# 1-13-2013.net
KiCad netlist of a schematic drawn in EAGLE
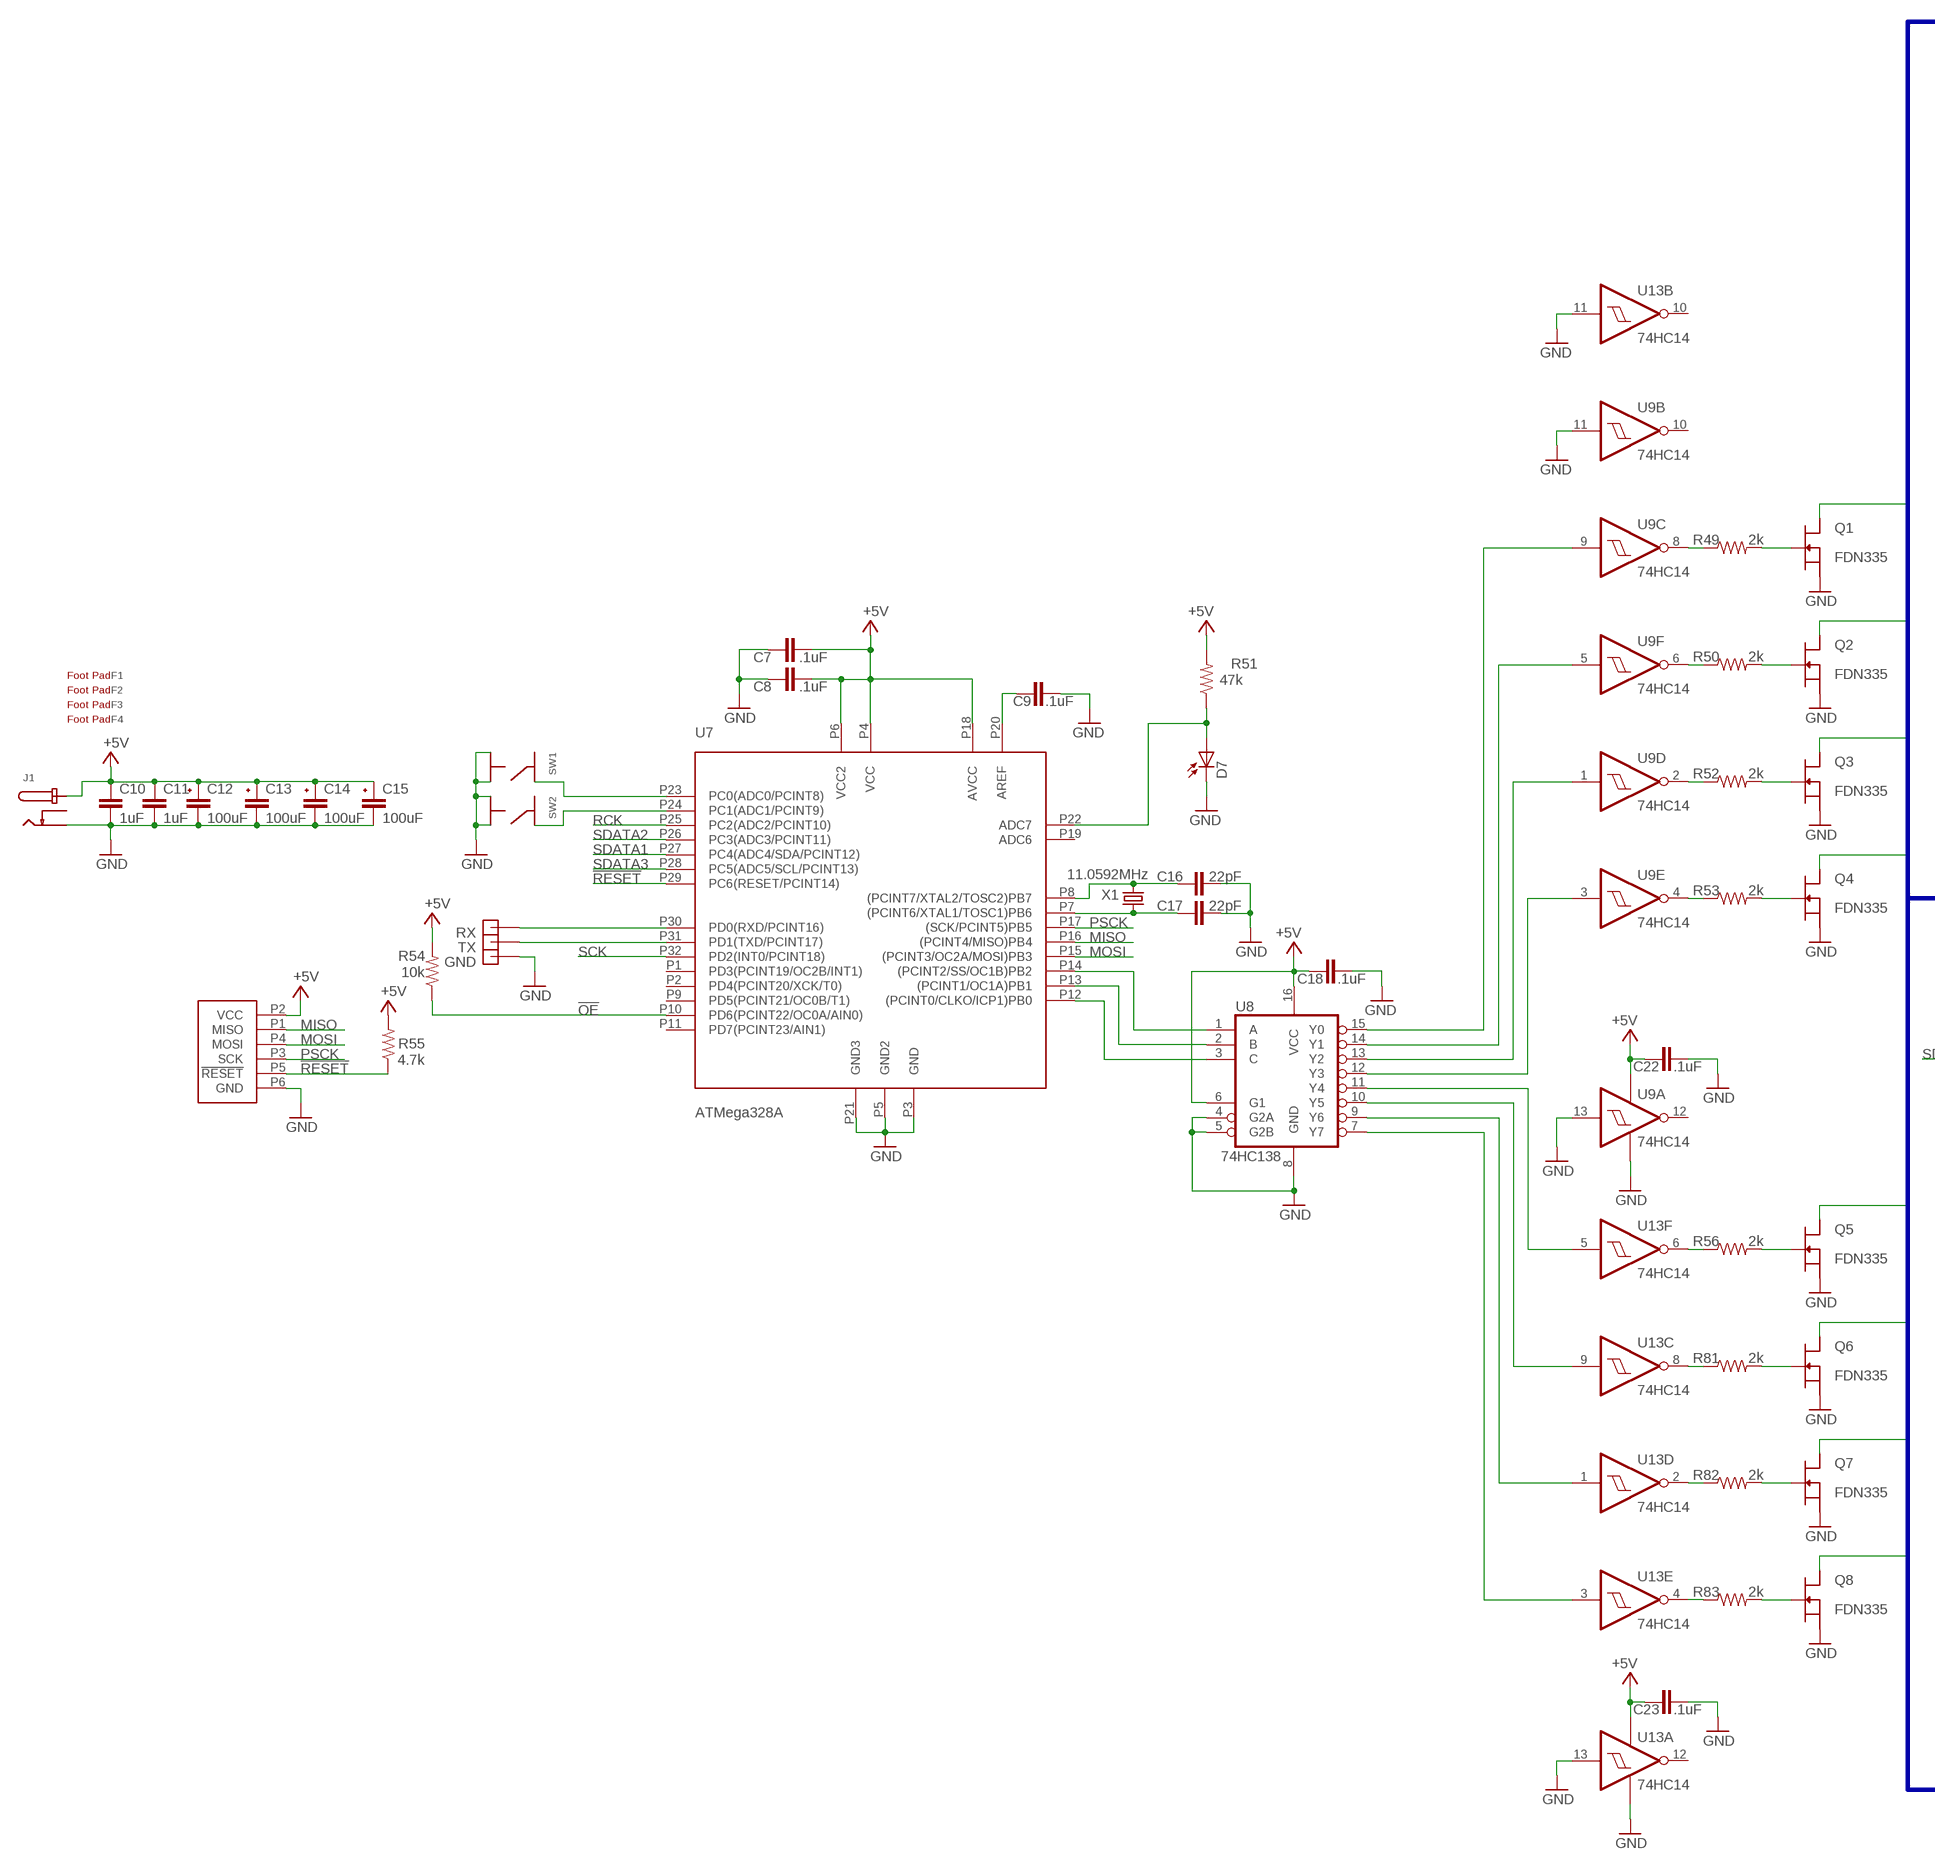
[diagram p0: schematic, sheet 1, part 1 of 2]
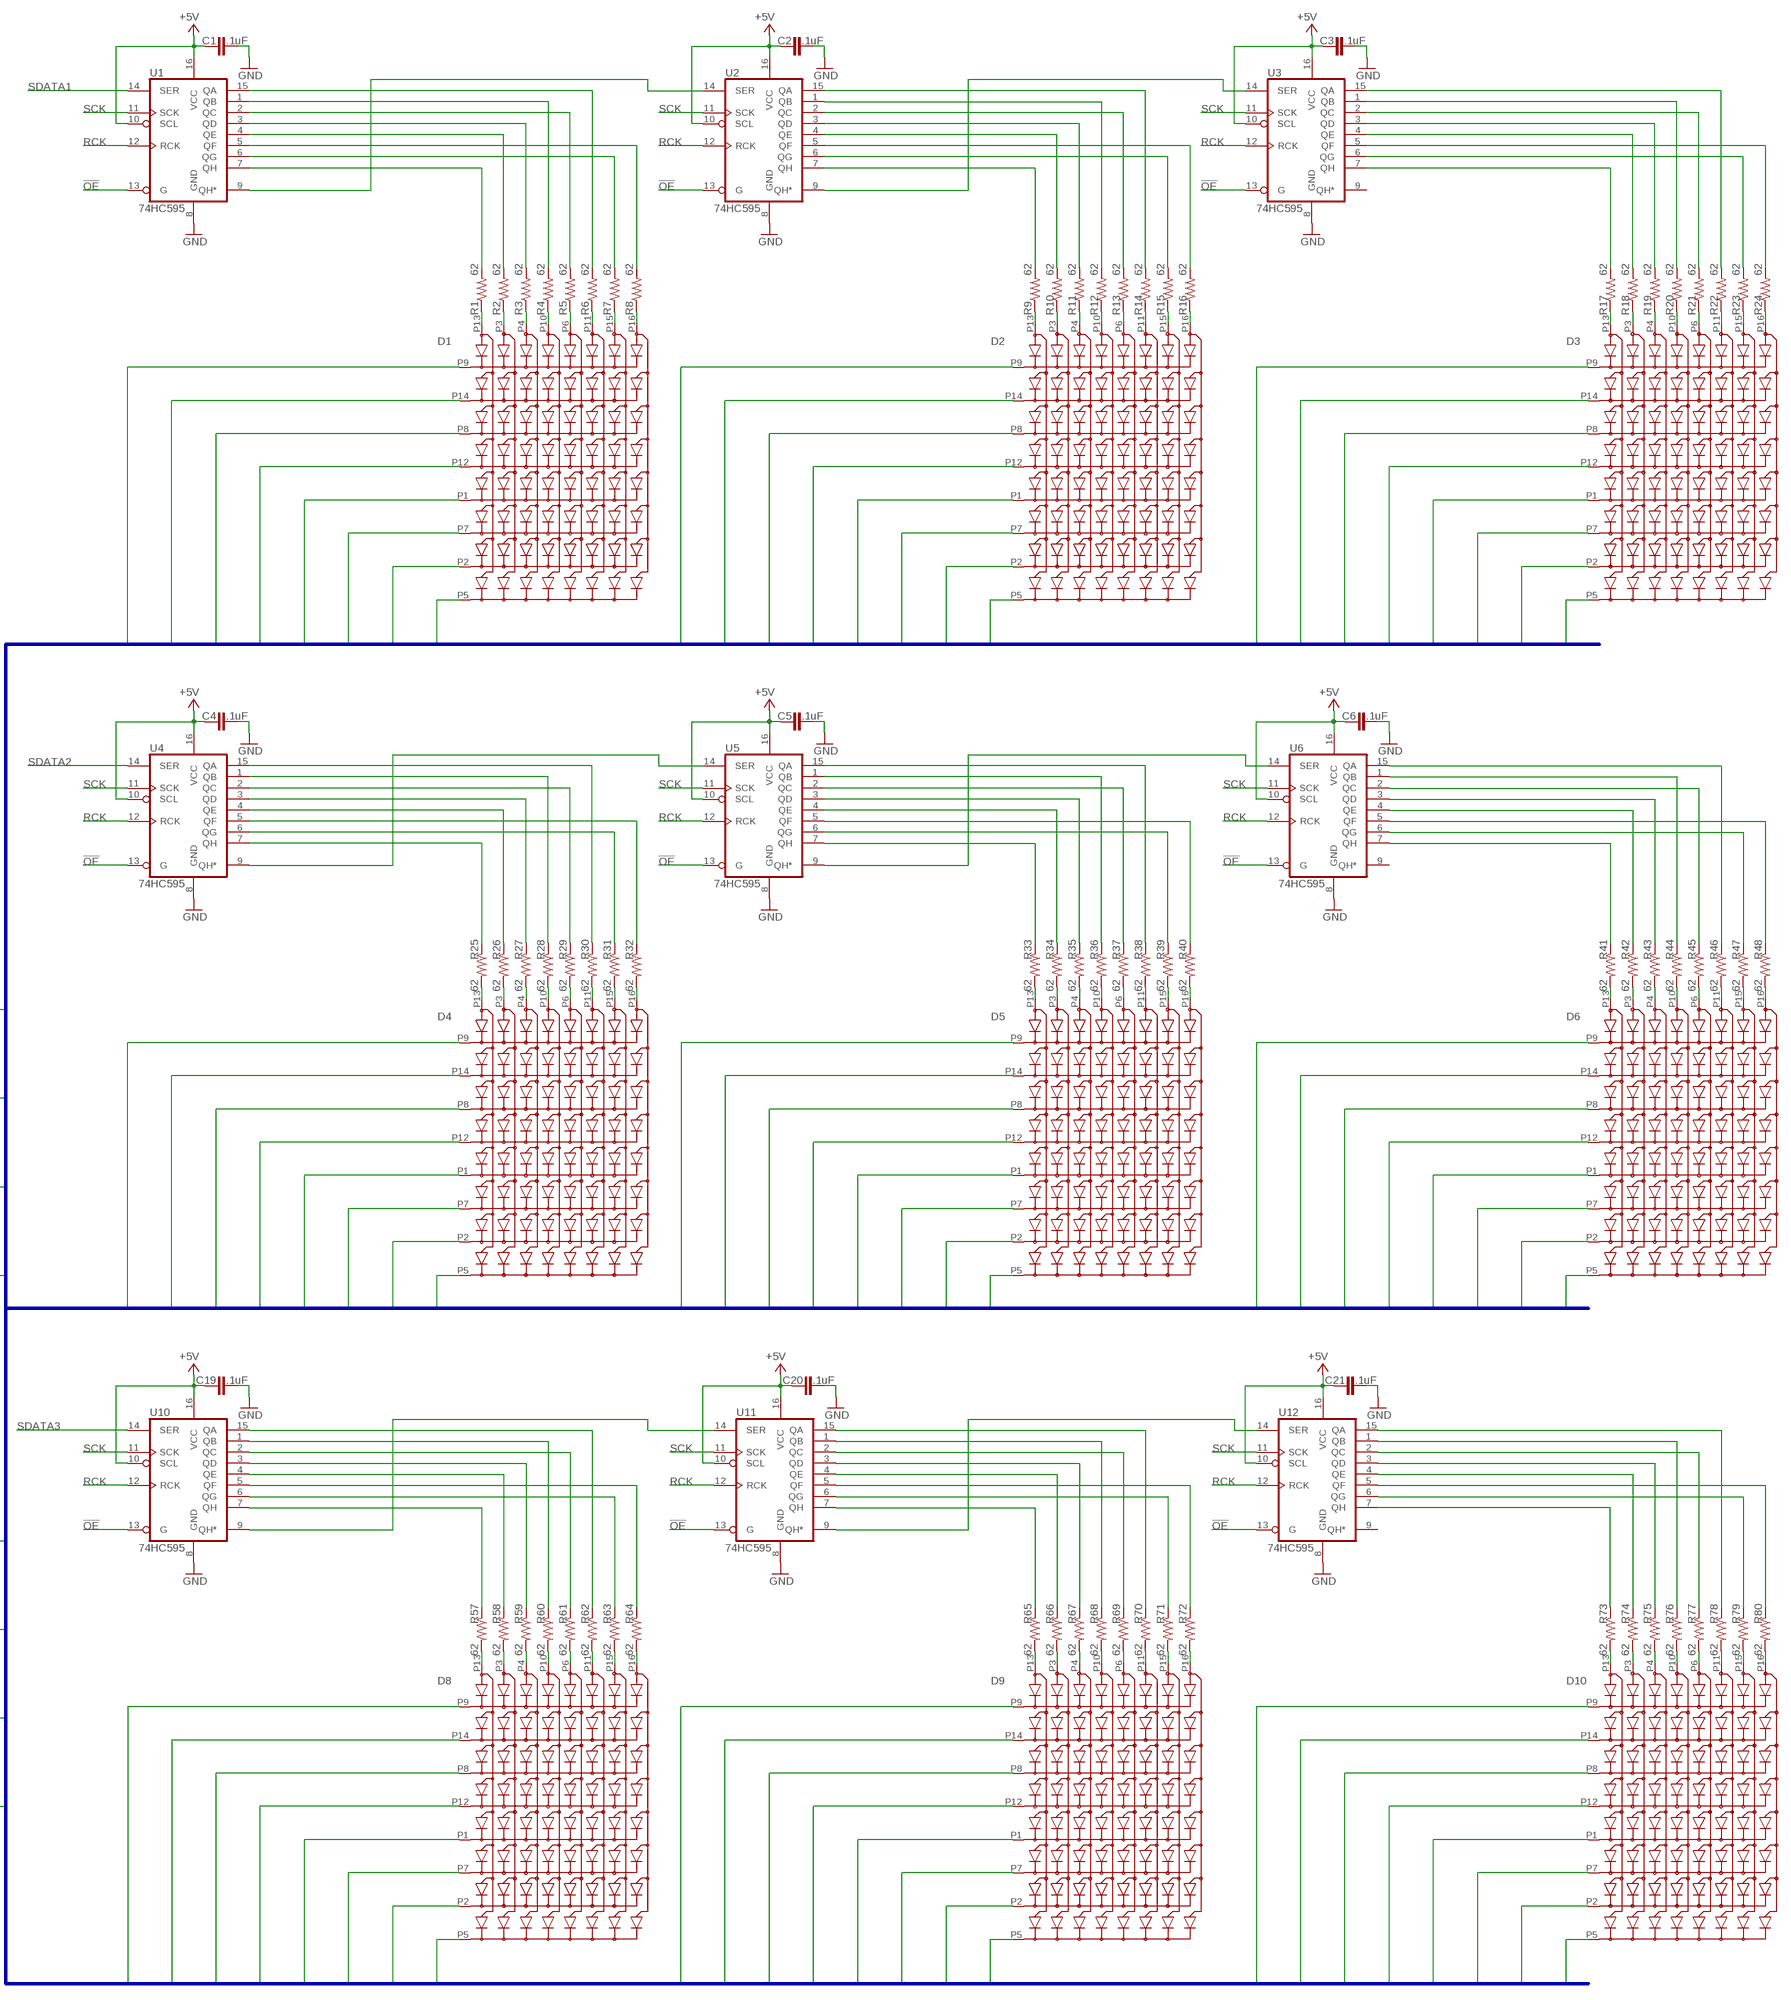
[diagram p1: schematic, sheet 1, part 2 of 2]

(export (version "E")
  (design (tool "Eeschema 10.0.6"))
  (components
    (comp (ref "C1")
      (value ".1uF")
      (footprint "eagle-import:0603_1608METRIC")
      (fields
        (field (name "DISTRIBUTORPARTNO") "478-1239-1-ND")
        (field (name "MANUFACTURER") "AVX Corporation")
        (field (name "TOLERANCE") "10%")
        (field (name "MNT-TYPE") "SM")
      )
      (libsource (lib "eagle-import") (part "CAPACITOR-.1UF"))
    )
    (comp (ref "C2")
      (value ".1uF")
      (footprint "eagle-import:0603_1608METRIC")
      (fields
        (field (name "DISTRIBUTORPARTNO") "478-1239-1-ND")
        (field (name "MANUFACTURER") "AVX Corporation")
        (field (name "TOLERANCE") "10%")
        (field (name "MNT-TYPE") "SM")
      )
      (libsource (lib "eagle-import") (part "CAPACITOR-.1UF"))
    )
    (comp (ref "C3")
      (value ".1uF")
      (footprint "eagle-import:0603_1608METRIC")
      (fields
        (field (name "DISTRIBUTORPARTNO") "478-1239-1-ND")
        (field (name "MANUFACTURER") "AVX Corporation")
        (field (name "TOLERANCE") "10%")
        (field (name "MNT-TYPE") "SM")
      )
      (libsource (lib "eagle-import") (part "CAPACITOR-.1UF"))
    )
    (comp (ref "C4")
      (value ".1uF")
      (footprint "eagle-import:0603_1608METRIC")
      (fields
        (field (name "DISTRIBUTORPARTNO") "478-1239-1-ND")
        (field (name "MANUFACTURER") "AVX Corporation")
        (field (name "TOLERANCE") "10%")
        (field (name "MNT-TYPE") "SM")
      )
      (libsource (lib "eagle-import") (part "CAPACITOR-.1UF"))
    )
    (comp (ref "C5")
      (value ".1uF")
      (footprint "eagle-import:0603_1608METRIC")
      (fields
        (field (name "DISTRIBUTORPARTNO") "478-1239-1-ND")
        (field (name "MANUFACTURER") "AVX Corporation")
        (field (name "TOLERANCE") "10%")
        (field (name "MNT-TYPE") "SM")
      )
      (libsource (lib "eagle-import") (part "CAPACITOR-.1UF"))
    )
    (comp (ref "C6")
      (value ".1uF")
      (footprint "eagle-import:0603_1608METRIC")
      (fields
        (field (name "DISTRIBUTORPARTNO") "478-1239-1-ND")
        (field (name "MANUFACTURER") "AVX Corporation")
        (field (name "TOLERANCE") "10%")
        (field (name "MNT-TYPE") "SM")
      )
      (libsource (lib "eagle-import") (part "CAPACITOR-.1UF"))
    )
    (comp (ref "C7")
      (value ".1uF")
      (footprint "eagle-import:0603_1608METRIC")
      (fields
        (field (name "DISTRIBUTORPARTNO") "478-1239-1-ND")
        (field (name "MANUFACTURER") "AVX Corporation")
        (field (name "TOLERANCE") "10%")
        (field (name "MNT-TYPE") "SM")
      )
      (libsource (lib "eagle-import") (part "CAPACITOR-.1UF"))
    )
    (comp (ref "C8")
      (value ".1uF")
      (footprint "eagle-import:0603_1608METRIC")
      (fields
        (field (name "DISTRIBUTORPARTNO") "478-1239-1-ND")
        (field (name "MANUFACTURER") "AVX Corporation")
        (field (name "TOLERANCE") "10%")
        (field (name "MNT-TYPE") "SM")
      )
      (libsource (lib "eagle-import") (part "CAPACITOR-.1UF"))
    )
    (comp (ref "C9")
      (value ".1uF")
      (footprint "eagle-import:0603_1608METRIC")
      (fields
        (field (name "DISTRIBUTORPARTNO") "478-1239-1-ND")
        (field (name "MANUFACTURER") "AVX Corporation")
        (field (name "TOLERANCE") "10%")
        (field (name "MNT-TYPE") "SM")
      )
      (libsource (lib "eagle-import") (part "CAPACITOR-.1UF"))
    )
    (comp (ref "C10")
      (value "1uF")
      (footprint "eagle-import:0603_1608METRIC")
      (fields
        (field (name "DISTRIBUTORPARTNO") "445-1328-1-ND")
        (field (name "MANUFACTURER") "TDK CORPORATION")
        (field (name "TOLERANCE") "20%")
      )
      (libsource (lib "eagle-import") (part "CAPACITOR-1UF"))
    )
    (comp (ref "C11")
      (value "1uF")
      (footprint "eagle-import:0603_1608METRIC")
      (fields
        (field (name "DISTRIBUTORPARTNO") "445-1328-1-ND")
        (field (name "MANUFACTURER") "TDK CORPORATION")
        (field (name "TOLERANCE") "20%")
      )
      (libsource (lib "eagle-import") (part "CAPACITOR-1UF"))
    )
    (comp (ref "C12")
      (value "100uF")
      (footprint "eagle-import:CAP-UWX-6.3")
      (fields
        (field (name "DISTRIBUTORPARTNO") "493-2105-1-ND")
        (field (name "MANPARTNO") "UWX1C101MCL1GB")
        (field (name "MANUFACTURER") "Nichicon")
      )
      (libsource (lib "eagle-import") (part "ELEC-100UF-SMT"))
    )
    (comp (ref "C13")
      (value "100uF")
      (footprint "eagle-import:CAP-UWX-6.3")
      (fields
        (field (name "DISTRIBUTORPARTNO") "493-2105-1-ND")
        (field (name "MANPARTNO") "UWX1C101MCL1GB")
        (field (name "MANUFACTURER") "Nichicon")
      )
      (libsource (lib "eagle-import") (part "ELEC-100UF-SMT"))
    )
    (comp (ref "C14")
      (value "100uF")
      (footprint "eagle-import:CAP-UWX-6.3")
      (description "CAP ALUM 100UF 16V 20% SMD")
      (fields
        (field (name "DISTRIBUTORPARTNO") "493-2105-1-ND")
        (field (name "MANPARTNO") "UWX1C101MCL1GB")
        (field (name "MANUFACTURER") "Nichicon")
        (field (name "DISTRIBUTOR") "Digikey")
        (field (name "DISTRIBUTORPARTNO_1") "493-2105-1-ND")
        (field (name "MANPARTNO_1") "UWX1C101MCL1GB")
        (field (name "MANUFACTURER_1") "Nichicon")
        (field (name "MNT-TYPE") "SM")
        (field (name "NO-PINS") "2")
        (field (name "PACKAGE") "RADIAL-SMT")
      )
      (libsource (lib "eagle-import") (part "ELEC-100UF-SMT"))
    )
    (comp (ref "C15")
      (value "100uF")
      (footprint "eagle-import:CAP-UWX-6.3")
      (description "CAP ALUM 100UF 16V 20% SMD")
      (fields
        (field (name "DISTRIBUTORPARTNO") "493-2105-1-ND")
        (field (name "MANPARTNO") "UWX1C101MCL1GB")
        (field (name "MANUFACTURER") "Nichicon")
        (field (name "DISTRIBUTOR") "Digikey")
        (field (name "DISTRIBUTORPARTNO_1") "493-2105-1-ND")
        (field (name "MANPARTNO_1") "UWX1C101MCL1GB")
        (field (name "MANUFACTURER_1") "Nichicon")
        (field (name "MNT-TYPE") "SM")
        (field (name "NO-PINS") "2")
        (field (name "PACKAGE") "RADIAL-SMT")
      )
      (libsource (lib "eagle-import") (part "ELEC-100UF-SMT"))
    )
    (comp (ref "C16")
      (value "22pF")
      (footprint "eagle-import:0603_1608METRIC")
      (description "CAP CER 22PF 25V 5% NP0 0603")
      (fields
        (field (name "DISTRIBUTORPARTNO") "478-6200-1-ND")
        (field (name "MANPARTNO") "06033A220JAT2A ")
        (field (name "MANUFACTURER") "AVX Corporation")
        (field (name "DISTRIBUTORPARTNO_1") "478-6200-1-ND")
        (field (name "MANUFACTURER_1") "AVX Corporation")
        (field (name "VOLTAGE") "25V")
      )
      (libsource (lib "eagle-import") (part "CAPACITOR-22PF"))
    )
    (comp (ref "C17")
      (value "22pF")
      (footprint "eagle-import:0603_1608METRIC")
      (description "CAP CER 22PF 25V 5% NP0 0603")
      (fields
        (field (name "DISTRIBUTORPARTNO") "478-6200-1-ND")
        (field (name "MANPARTNO") "06033A220JAT2A ")
        (field (name "MANUFACTURER") "AVX Corporation")
        (field (name "DISTRIBUTORPARTNO_1") "478-6200-1-ND")
        (field (name "MANUFACTURER_1") "AVX Corporation")
        (field (name "VOLTAGE") "25V")
      )
      (libsource (lib "eagle-import") (part "CAPACITOR-22PF"))
    )
    (comp (ref "C18")
      (value ".1uF")
      (footprint "eagle-import:0603_1608METRIC")
      (fields
        (field (name "DISTRIBUTORPARTNO") "478-1239-1-ND")
        (field (name "MANUFACTURER") "AVX Corporation")
        (field (name "TOLERANCE") "10%")
        (field (name "MNT-TYPE") "SM")
      )
      (libsource (lib "eagle-import") (part "CAPACITOR-.1UF"))
    )
    (comp (ref "C19")
      (value ".1uF")
      (footprint "eagle-import:0603_1608METRIC")
      (fields
        (field (name "DISTRIBUTORPARTNO") "478-1239-1-ND")
        (field (name "MANUFACTURER") "AVX Corporation")
        (field (name "TOLERANCE") "10%")
        (field (name "MNT-TYPE") "SM")
      )
      (libsource (lib "eagle-import") (part "CAPACITOR-.1UF"))
    )
    (comp (ref "C20")
      (value ".1uF")
      (footprint "eagle-import:0603_1608METRIC")
      (fields
        (field (name "DISTRIBUTORPARTNO") "478-1239-1-ND")
        (field (name "MANUFACTURER") "AVX Corporation")
        (field (name "TOLERANCE") "10%")
        (field (name "MNT-TYPE") "SM")
      )
      (libsource (lib "eagle-import") (part "CAPACITOR-.1UF"))
    )
    (comp (ref "C21")
      (value ".1uF")
      (footprint "eagle-import:0603_1608METRIC")
      (fields
        (field (name "DISTRIBUTORPARTNO") "478-1239-1-ND")
        (field (name "MANUFACTURER") "AVX Corporation")
        (field (name "TOLERANCE") "10%")
        (field (name "MNT-TYPE") "SM")
      )
      (libsource (lib "eagle-import") (part "CAPACITOR-.1UF"))
    )
    (comp (ref "C22")
      (value ".1uF")
      (footprint "eagle-import:0603_1608METRIC")
      (fields
        (field (name "DISTRIBUTORPARTNO") "478-1239-1-ND")
        (field (name "MANUFACTURER") "AVX Corporation")
        (field (name "TOLERANCE") "10%")
        (field (name "MNT-TYPE") "SM")
      )
      (libsource (lib "eagle-import") (part "CAPACITOR-.1UF"))
    )
    (comp (ref "C23")
      (value ".1uF")
      (footprint "eagle-import:0603_1608METRIC")
      (fields
        (field (name "DISTRIBUTORPARTNO") "478-1239-1-ND")
        (field (name "MANUFACTURER") "AVX Corporation")
        (field (name "TOLERANCE") "10%")
        (field (name "MNT-TYPE") "SM")
      )
      (libsource (lib "eagle-import") (part "CAPACITOR-.1UF"))
    )
    (comp (ref "D1")
      (value "WHITE")
      (footprint "eagle-import:HS-2085BX")
      (fields
        (field (name "DISTRIBUTORPARTNO") "HS-2085AWND")
        (field (name "MANUFACTURER") "XINDALI ELECTRONICS")
      )
      (libsource (lib "eagle-import") (part "HS-2085AND-W"))
    )
    (comp (ref "D2")
      (value "WHITE")
      (footprint "eagle-import:HS-2085BX")
      (fields
        (field (name "DISTRIBUTORPARTNO") "HS-2085AWND")
        (field (name "MANUFACTURER") "XINDALI ELECTRONICS")
      )
      (libsource (lib "eagle-import") (part "HS-2085AND-W"))
    )
    (comp (ref "D3")
      (value "WHITE")
      (footprint "eagle-import:HS-2085BX")
      (fields
        (field (name "DISTRIBUTORPARTNO") "HS-2085AWND")
        (field (name "MANUFACTURER") "XINDALI ELECTRONICS")
      )
      (libsource (lib "eagle-import") (part "HS-2085AND-W"))
    )
    (comp (ref "D4")
      (value "WHITE")
      (footprint "eagle-import:HS-2085BX")
      (fields
        (field (name "DISTRIBUTORPARTNO") "HS-2085AWND")
        (field (name "MANUFACTURER") "XINDALI ELECTRONICS")
      )
      (libsource (lib "eagle-import") (part "HS-2085AND-W"))
    )
    (comp (ref "D5")
      (value "WHITE")
      (footprint "eagle-import:HS-2085BX")
      (fields
        (field (name "DISTRIBUTORPARTNO") "HS-2085AWND")
        (field (name "MANUFACTURER") "XINDALI ELECTRONICS")
      )
      (libsource (lib "eagle-import") (part "HS-2085AND-W"))
    )
    (comp (ref "D6")
      (value "WHITE")
      (footprint "eagle-import:HS-2085BX")
      (fields
        (field (name "DISTRIBUTORPARTNO") "HS-2085AWND")
        (field (name "MANUFACTURER") "XINDALI ELECTRONICS")
      )
      (libsource (lib "eagle-import") (part "HS-2085AND-W"))
    )
    (comp (ref "D7")
      (value "TEPT4400")
      (footprint "eagle-import:LED3MM")
      (fields
        (field (name "DISTRIBUTORPARTNO") "751-1057-ND")
        (field (name "MANUFACTURER") "Vishay Semiconductors")
      )
      (libsource (lib "eagle-import") (part "TEPT4400"))
    )
    (comp (ref "D8")
      (value "WHITE")
      (footprint "eagle-import:HS-2085BX")
      (fields
        (field (name "DISTRIBUTORPARTNO") "HS-2085AWND")
        (field (name "MANUFACTURER") "XINDALI ELECTRONICS")
      )
      (libsource (lib "eagle-import") (part "HS-2085AND-W"))
    )
    (comp (ref "D9")
      (value "WHITE")
      (footprint "eagle-import:HS-2085BX")
      (fields
        (field (name "DISTRIBUTORPARTNO") "HS-2085AWND")
        (field (name "MANUFACTURER") "XINDALI ELECTRONICS")
      )
      (libsource (lib "eagle-import") (part "HS-2085AND-W"))
    )
    (comp (ref "D10")
      (value "WHITE")
      (footprint "eagle-import:HS-2085BX")
      (fields
        (field (name "DISTRIBUTORPARTNO") "HS-2085AWND")
        (field (name "MANUFACTURER") "XINDALI ELECTRONICS")
      )
      (libsource (lib "eagle-import") (part "HS-2085AND-W"))
    )
    (comp (ref "F1")
      (value "RUBBER-FOOT")
      (footprint "eagle-import:SJ-5518")
      (fields
        (field (name "DISTRIBUTORPARTNO") "SJ5518-0-ND")
        (field (name "MANPARTNO") "SJ-5518 (BLACK)")
        (field (name "MANUFACTURER") "3M")
      )
      (libsource (lib "eagle-import") (part "RUBBER-FOOT"))
    )
    (comp (ref "F2")
      (value "RUBBER-FOOT")
      (footprint "eagle-import:SJ-5518")
      (fields
        (field (name "DISTRIBUTORPARTNO") "SJ5518-0-ND")
        (field (name "MANPARTNO") "SJ-5518 (BLACK)")
        (field (name "MANUFACTURER") "3M")
      )
      (libsource (lib "eagle-import") (part "RUBBER-FOOT"))
    )
    (comp (ref "F3")
      (value "RUBBER-FOOT")
      (footprint "eagle-import:SJ-5518")
      (fields
        (field (name "DISTRIBUTORPARTNO") "SJ5518-0-ND")
        (field (name "MANPARTNO") "SJ-5518 (BLACK)")
        (field (name "MANUFACTURER") "3M")
      )
      (libsource (lib "eagle-import") (part "RUBBER-FOOT"))
    )
    (comp (ref "F4")
      (value "RUBBER-FOOT")
      (footprint "eagle-import:SJ-5518")
      (fields
        (field (name "DISTRIBUTORPARTNO") "SJ5518-0-ND")
        (field (name "MANPARTNO") "SJ-5518 (BLACK)")
        (field (name "MANUFACTURER") "3M")
      )
      (libsource (lib "eagle-import") (part "RUBBER-FOOT"))
    )
    (comp (ref "GND")
      (value "HEADERPIN")
      (footprint "eagle-import:HEADERPIN")
      (libsource (lib "eagle-import") (part "HEADERPIN"))
    )
    (comp (ref "J1")
      (value "DC-BARREL-JACK-SWITCH")
      (footprint "eagle-import:PJ-075DH-SMT-TR")
      (fields
        (field (name "DISTRIBUTORPARTNO") "CP-075DHPJCT-ND")
        (field (name "MANPARTNO") "PJ-075DH-SMT-TR")
        (field (name "MANUFACTURER") "CUI Inc")
      )
      (libsource (lib "eagle-import") (part "DC-BARREL-JACK-SWITCH"))
    )
    (comp (ref "J2")
      (value "PROGHEADER-PINS")
      (footprint "eagle-import:ATMEL-PROGRAMMING-HEADER")
      (fields
        (field (name "DISTRIBUTORPARTNO") "xxSAM1048-50-NDxx")
        (field (name "MANPARTNO") "TSW-150-08-T-D")
        (field (name "MANUFACTURER") "Samtec Inc.")
      )
      (libsource (lib "eagle-import") (part "PROGHEADER-PINS"))
    )
    (comp (ref "Q1")
      (value "FDN335")
      (footprint "eagle-import:SOT23")
      (fields
        (field (name "DISTRIBUTORPARTNO") "FDN335NCT-ND")
        (field (name "MANPARTNO") "FDN335N")
        (field (name "MANUFACTURER") "Fairchild Semiconductor")
      )
      (libsource (lib "eagle-import") (part "FDN335"))
    )
    (comp (ref "Q2")
      (value "FDN335")
      (footprint "eagle-import:SOT23")
      (fields
        (field (name "DISTRIBUTORPARTNO") "FDN335NCT-ND")
        (field (name "MANPARTNO") "FDN335N")
        (field (name "MANUFACTURER") "Fairchild Semiconductor")
      )
      (libsource (lib "eagle-import") (part "FDN335"))
    )
    (comp (ref "Q3")
      (value "FDN335")
      (footprint "eagle-import:SOT23")
      (fields
        (field (name "DISTRIBUTORPARTNO") "FDN335NCT-ND")
        (field (name "MANPARTNO") "FDN335N")
        (field (name "MANUFACTURER") "Fairchild Semiconductor")
      )
      (libsource (lib "eagle-import") (part "FDN335"))
    )
    (comp (ref "Q4")
      (value "FDN335")
      (footprint "eagle-import:SOT23")
      (fields
        (field (name "DISTRIBUTORPARTNO") "FDN335NCT-ND")
        (field (name "MANPARTNO") "FDN335N")
        (field (name "MANUFACTURER") "Fairchild Semiconductor")
      )
      (libsource (lib "eagle-import") (part "FDN335"))
    )
    (comp (ref "Q5")
      (value "FDN335")
      (footprint "eagle-import:SOT23")
      (fields
        (field (name "DISTRIBUTORPARTNO") "FDN335NCT-ND")
        (field (name "MANPARTNO") "FDN335N")
        (field (name "MANUFACTURER") "Fairchild Semiconductor")
      )
      (libsource (lib "eagle-import") (part "FDN335"))
    )
    (comp (ref "Q6")
      (value "FDN335")
      (footprint "eagle-import:SOT23")
      (fields
        (field (name "DISTRIBUTORPARTNO") "FDN335NCT-ND")
        (field (name "MANPARTNO") "FDN335N")
        (field (name "MANUFACTURER") "Fairchild Semiconductor")
      )
      (libsource (lib "eagle-import") (part "FDN335"))
    )
    (comp (ref "Q7")
      (value "FDN335")
      (footprint "eagle-import:SOT23")
      (fields
        (field (name "DISTRIBUTORPARTNO") "FDN335NCT-ND")
        (field (name "MANPARTNO") "FDN335N")
        (field (name "MANUFACTURER") "Fairchild Semiconductor")
      )
      (libsource (lib "eagle-import") (part "FDN335"))
    )
    (comp (ref "Q8")
      (value "FDN335")
      (footprint "eagle-import:SOT23")
      (fields
        (field (name "DISTRIBUTORPARTNO") "FDN335NCT-ND")
        (field (name "MANPARTNO") "FDN335N")
        (field (name "MANUFACTURER") "Fairchild Semiconductor")
      )
      (libsource (lib "eagle-import") (part "FDN335"))
    )
    (comp (ref "R1")
      (value "62")
      (footprint "eagle-import:0603_1608METRIC")
      (fields
        (field (name "DISTRIBUTORPARTNO") "311-62GRCT-ND ")
        (field (name "MANPARTNO") "RC0603JR-0762RL ")
        (field (name "MANUFACTURER") "Yaego")
      )
      (libsource (lib "eagle-import") (part "RESISTOR--5%-060362"))
    )
    (comp (ref "R2")
      (value "62")
      (footprint "eagle-import:0603_1608METRIC")
      (description "RES 62 OHM 1/10W 5% 0603 SMD")
      (fields
        (field (name "DISTRIBUTORPARTNO") "311-62GRCT-ND ")
        (field (name "MANPARTNO") "RC0603JR-0762RL ")
        (field (name "MANUFACTURER") "Yaego")
        (field (name "DISTRIBUTOR") "Digikey")
        (field (name "DISTRIBUTORPARTNO_1") "311-62GRCT-ND ")
        (field (name "MANPARTNO_1") "RC0603JR-0762RL ")
        (field (name "MANUFACTURER_1") "Yaego")
        (field (name "MNT-TYPE") "SM")
        (field (name "NO-PINS") "2")
        (field (name "PACKAGE") "0603 (16080 Metric)")
        (field (name "TOLERANCE") "5%")
      )
      (libsource (lib "eagle-import") (part "RESISTOR--5%-060362"))
    )
    (comp (ref "R3")
      (value "62")
      (footprint "eagle-import:0603_1608METRIC")
      (description "RES 62 OHM 1/10W 5% 0603 SMD")
      (fields
        (field (name "DISTRIBUTORPARTNO") "311-62GRCT-ND ")
        (field (name "MANPARTNO") "RC0603JR-0762RL ")
        (field (name "MANUFACTURER") "Yaego")
        (field (name "DISTRIBUTOR") "Digikey")
        (field (name "DISTRIBUTORPARTNO_1") "311-62GRCT-ND ")
        (field (name "MANPARTNO_1") "RC0603JR-0762RL ")
        (field (name "MANUFACTURER_1") "Yaego")
        (field (name "MNT-TYPE") "SM")
        (field (name "NO-PINS") "2")
        (field (name "PACKAGE") "0603 (16080 Metric)")
        (field (name "TOLERANCE") "5%")
      )
      (libsource (lib "eagle-import") (part "RESISTOR--5%-060362"))
    )
    (comp (ref "R4")
      (value "62")
      (footprint "eagle-import:0603_1608METRIC")
      (description "RES 62 OHM 1/10W 5% 0603 SMD")
      (fields
        (field (name "DISTRIBUTORPARTNO") "311-62GRCT-ND ")
        (field (name "MANPARTNO") "RC0603JR-0762RL ")
        (field (name "MANUFACTURER") "Yaego")
        (field (name "DISTRIBUTOR") "Digikey")
        (field (name "DISTRIBUTORPARTNO_1") "311-62GRCT-ND ")
        (field (name "MANPARTNO_1") "RC0603JR-0762RL ")
        (field (name "MANUFACTURER_1") "Yaego")
        (field (name "MNT-TYPE") "SM")
        (field (name "NO-PINS") "2")
        (field (name "PACKAGE") "0603 (16080 Metric)")
        (field (name "TOLERANCE") "5%")
      )
      (libsource (lib "eagle-import") (part "RESISTOR--5%-060362"))
    )
    (comp (ref "R5")
      (value "62")
      (footprint "eagle-import:0603_1608METRIC")
      (description "RES 62 OHM 1/10W 5% 0603 SMD")
      (fields
        (field (name "DISTRIBUTORPARTNO") "311-62GRCT-ND ")
        (field (name "MANPARTNO") "RC0603JR-0762RL ")
        (field (name "MANUFACTURER") "Yaego")
        (field (name "DISTRIBUTOR") "Digikey")
        (field (name "DISTRIBUTORPARTNO_1") "311-62GRCT-ND ")
        (field (name "MANPARTNO_1") "RC0603JR-0762RL ")
        (field (name "MANUFACTURER_1") "Yaego")
        (field (name "MNT-TYPE") "SM")
        (field (name "NO-PINS") "2")
        (field (name "PACKAGE") "0603 (16080 Metric)")
        (field (name "TOLERANCE") "5%")
      )
      (libsource (lib "eagle-import") (part "RESISTOR--5%-060362"))
    )
    (comp (ref "R6")
      (value "62")
      (footprint "eagle-import:0603_1608METRIC")
      (description "RES 62 OHM 1/10W 5% 0603 SMD")
      (fields
        (field (name "DISTRIBUTORPARTNO") "311-62GRCT-ND ")
        (field (name "MANPARTNO") "RC0603JR-0762RL ")
        (field (name "MANUFACTURER") "Yaego")
        (field (name "DISTRIBUTOR") "Digikey")
        (field (name "DISTRIBUTORPARTNO_1") "311-62GRCT-ND ")
        (field (name "MANPARTNO_1") "RC0603JR-0762RL ")
        (field (name "MANUFACTURER_1") "Yaego")
        (field (name "MNT-TYPE") "SM")
        (field (name "NO-PINS") "2")
        (field (name "PACKAGE") "0603 (16080 Metric)")
        (field (name "TOLERANCE") "5%")
      )
      (libsource (lib "eagle-import") (part "RESISTOR--5%-060362"))
    )
    (comp (ref "R7")
      (value "62")
      (footprint "eagle-import:0603_1608METRIC")
      (description "RES 62 OHM 1/10W 5% 0603 SMD")
      (fields
        (field (name "DISTRIBUTORPARTNO") "311-62GRCT-ND ")
        (field (name "MANPARTNO") "RC0603JR-0762RL ")
        (field (name "MANUFACTURER") "Yaego")
        (field (name "DISTRIBUTOR") "Digikey")
        (field (name "DISTRIBUTORPARTNO_1") "311-62GRCT-ND ")
        (field (name "MANPARTNO_1") "RC0603JR-0762RL ")
        (field (name "MANUFACTURER_1") "Yaego")
        (field (name "MNT-TYPE") "SM")
        (field (name "NO-PINS") "2")
        (field (name "PACKAGE") "0603 (16080 Metric)")
        (field (name "TOLERANCE") "5%")
      )
      (libsource (lib "eagle-import") (part "RESISTOR--5%-060362"))
    )
    (comp (ref "R8")
      (value "62")
      (footprint "eagle-import:0603_1608METRIC")
      (description "RES 62 OHM 1/10W 5% 0603 SMD")
      (fields
        (field (name "DISTRIBUTORPARTNO") "311-62GRCT-ND ")
        (field (name "MANPARTNO") "RC0603JR-0762RL ")
        (field (name "MANUFACTURER") "Yaego")
        (field (name "DISTRIBUTOR") "Digikey")
        (field (name "DISTRIBUTORPARTNO_1") "311-62GRCT-ND ")
        (field (name "MANPARTNO_1") "RC0603JR-0762RL ")
        (field (name "MANUFACTURER_1") "Yaego")
        (field (name "MNT-TYPE") "SM")
        (field (name "NO-PINS") "2")
        (field (name "PACKAGE") "0603 (16080 Metric)")
        (field (name "TOLERANCE") "5%")
      )
      (libsource (lib "eagle-import") (part "RESISTOR--5%-060362"))
    )
    (comp (ref "R9")
      (value "62")
      (footprint "eagle-import:0603_1608METRIC")
      (description "RES 62 OHM 1/10W 5% 0603 SMD")
      (fields
        (field (name "DISTRIBUTORPARTNO") "311-62GRCT-ND ")
        (field (name "MANPARTNO") "RC0603JR-0762RL ")
        (field (name "MANUFACTURER") "Yaego")
        (field (name "DISTRIBUTOR") "Digikey")
        (field (name "DISTRIBUTORPARTNO_1") "311-62GRCT-ND ")
        (field (name "MANPARTNO_1") "RC0603JR-0762RL ")
        (field (name "MANUFACTURER_1") "Yaego")
        (field (name "MNT-TYPE") "SM")
        (field (name "NO-PINS") "2")
        (field (name "PACKAGE") "0603 (16080 Metric)")
        (field (name "TOLERANCE") "5%")
      )
      (libsource (lib "eagle-import") (part "RESISTOR--5%-060362"))
    )
    (comp (ref "R10")
      (value "62")
      (footprint "eagle-import:0603_1608METRIC")
      (description "RES 62 OHM 1/10W 5% 0603 SMD")
      (fields
        (field (name "DISTRIBUTORPARTNO") "311-62GRCT-ND ")
        (field (name "MANPARTNO") "RC0603JR-0762RL ")
        (field (name "MANUFACTURER") "Yaego")
        (field (name "DISTRIBUTOR") "Digikey")
        (field (name "DISTRIBUTORPARTNO_1") "311-62GRCT-ND ")
        (field (name "MANPARTNO_1") "RC0603JR-0762RL ")
        (field (name "MANUFACTURER_1") "Yaego")
        (field (name "MNT-TYPE") "SM")
        (field (name "NO-PINS") "2")
        (field (name "PACKAGE") "0603 (16080 Metric)")
        (field (name "TOLERANCE") "5%")
      )
      (libsource (lib "eagle-import") (part "RESISTOR--5%-060362"))
    )
    (comp (ref "R11")
      (value "62")
      (footprint "eagle-import:0603_1608METRIC")
      (description "RES 62 OHM 1/10W 5% 0603 SMD")
      (fields
        (field (name "DISTRIBUTORPARTNO") "311-62GRCT-ND ")
        (field (name "MANPARTNO") "RC0603JR-0762RL ")
        (field (name "MANUFACTURER") "Yaego")
        (field (name "DISTRIBUTOR") "Digikey")
        (field (name "DISTRIBUTORPARTNO_1") "311-62GRCT-ND ")
        (field (name "MANPARTNO_1") "RC0603JR-0762RL ")
        (field (name "MANUFACTURER_1") "Yaego")
        (field (name "MNT-TYPE") "SM")
        (field (name "NO-PINS") "2")
        (field (name "PACKAGE") "0603 (16080 Metric)")
        (field (name "TOLERANCE") "5%")
      )
      (libsource (lib "eagle-import") (part "RESISTOR--5%-060362"))
    )
    (comp (ref "R12")
      (value "62")
      (footprint "eagle-import:0603_1608METRIC")
      (description "RES 62 OHM 1/10W 5% 0603 SMD")
      (fields
        (field (name "DISTRIBUTORPARTNO") "311-62GRCT-ND ")
        (field (name "MANPARTNO") "RC0603JR-0762RL ")
        (field (name "MANUFACTURER") "Yaego")
        (field (name "DISTRIBUTOR") "Digikey")
        (field (name "DISTRIBUTORPARTNO_1") "311-62GRCT-ND ")
        (field (name "MANPARTNO_1") "RC0603JR-0762RL ")
        (field (name "MANUFACTURER_1") "Yaego")
        (field (name "MNT-TYPE") "SM")
        (field (name "NO-PINS") "2")
        (field (name "PACKAGE") "0603 (16080 Metric)")
        (field (name "TOLERANCE") "5%")
      )
      (libsource (lib "eagle-import") (part "RESISTOR--5%-060362"))
    )
    (comp (ref "R13")
      (value "62")
      (footprint "eagle-import:0603_1608METRIC")
      (description "RES 62 OHM 1/10W 5% 0603 SMD")
      (fields
        (field (name "DISTRIBUTORPARTNO") "311-62GRCT-ND ")
        (field (name "MANPARTNO") "RC0603JR-0762RL ")
        (field (name "MANUFACTURER") "Yaego")
        (field (name "DISTRIBUTOR") "Digikey")
        (field (name "DISTRIBUTORPARTNO_1") "311-62GRCT-ND ")
        (field (name "MANPARTNO_1") "RC0603JR-0762RL ")
        (field (name "MANUFACTURER_1") "Yaego")
        (field (name "MNT-TYPE") "SM")
        (field (name "NO-PINS") "2")
        (field (name "PACKAGE") "0603 (16080 Metric)")
        (field (name "TOLERANCE") "5%")
      )
      (libsource (lib "eagle-import") (part "RESISTOR--5%-060362"))
    )
    (comp (ref "R14")
      (value "62")
      (footprint "eagle-import:0603_1608METRIC")
      (description "RES 62 OHM 1/10W 5% 0603 SMD")
      (fields
        (field (name "DISTRIBUTORPARTNO") "311-62GRCT-ND ")
        (field (name "MANPARTNO") "RC0603JR-0762RL ")
        (field (name "MANUFACTURER") "Yaego")
        (field (name "DISTRIBUTOR") "Digikey")
        (field (name "DISTRIBUTORPARTNO_1") "311-62GRCT-ND ")
        (field (name "MANPARTNO_1") "RC0603JR-0762RL ")
        (field (name "MANUFACTURER_1") "Yaego")
        (field (name "MNT-TYPE") "SM")
        (field (name "NO-PINS") "2")
        (field (name "PACKAGE") "0603 (16080 Metric)")
        (field (name "TOLERANCE") "5%")
      )
      (libsource (lib "eagle-import") (part "RESISTOR--5%-060362"))
    )
    (comp (ref "R15")
      (value "62")
      (footprint "eagle-import:0603_1608METRIC")
      (description "RES 62 OHM 1/10W 5% 0603 SMD")
      (fields
        (field (name "DISTRIBUTORPARTNO") "311-62GRCT-ND ")
        (field (name "MANPARTNO") "RC0603JR-0762RL ")
        (field (name "MANUFACTURER") "Yaego")
        (field (name "DISTRIBUTOR") "Digikey")
        (field (name "DISTRIBUTORPARTNO_1") "311-62GRCT-ND ")
        (field (name "MANPARTNO_1") "RC0603JR-0762RL ")
        (field (name "MANUFACTURER_1") "Yaego")
        (field (name "MNT-TYPE") "SM")
        (field (name "NO-PINS") "2")
        (field (name "PACKAGE") "0603 (16080 Metric)")
        (field (name "TOLERANCE") "5%")
      )
      (libsource (lib "eagle-import") (part "RESISTOR--5%-060362"))
    )
    (comp (ref "R16")
      (value "62")
      (footprint "eagle-import:0603_1608METRIC")
      (description "RES 62 OHM 1/10W 5% 0603 SMD")
      (fields
        (field (name "DISTRIBUTORPARTNO") "311-62GRCT-ND ")
        (field (name "MANPARTNO") "RC0603JR-0762RL ")
        (field (name "MANUFACTURER") "Yaego")
        (field (name "DISTRIBUTOR") "Digikey")
        (field (name "DISTRIBUTORPARTNO_1") "311-62GRCT-ND ")
        (field (name "MANPARTNO_1") "RC0603JR-0762RL ")
        (field (name "MANUFACTURER_1") "Yaego")
        (field (name "MNT-TYPE") "SM")
        (field (name "NO-PINS") "2")
        (field (name "PACKAGE") "0603 (16080 Metric)")
        (field (name "TOLERANCE") "5%")
      )
      (libsource (lib "eagle-import") (part "RESISTOR--5%-060362"))
    )
    (comp (ref "R17")
      (value "62")
      (footprint "eagle-import:0603_1608METRIC")
      (description "RES 62 OHM 1/10W 5% 0603 SMD")
      (fields
        (field (name "DISTRIBUTORPARTNO") "311-62GRCT-ND ")
        (field (name "MANPARTNO") "RC0603JR-0762RL ")
        (field (name "MANUFACTURER") "Yaego")
        (field (name "DISTRIBUTOR") "Digikey")
        (field (name "DISTRIBUTORPARTNO_1") "311-62GRCT-ND ")
        (field (name "MANPARTNO_1") "RC0603JR-0762RL ")
        (field (name "MANUFACTURER_1") "Yaego")
        (field (name "MNT-TYPE") "SM")
        (field (name "NO-PINS") "2")
        (field (name "PACKAGE") "0603 (16080 Metric)")
        (field (name "TOLERANCE") "5%")
      )
      (libsource (lib "eagle-import") (part "RESISTOR--5%-060362"))
    )
    (comp (ref "R18")
      (value "62")
      (footprint "eagle-import:0603_1608METRIC")
      (description "RES 62 OHM 1/10W 5% 0603 SMD")
      (fields
        (field (name "DISTRIBUTORPARTNO") "311-62GRCT-ND ")
        (field (name "MANPARTNO") "RC0603JR-0762RL ")
        (field (name "MANUFACTURER") "Yaego")
        (field (name "DISTRIBUTOR") "Digikey")
        (field (name "DISTRIBUTORPARTNO_1") "311-62GRCT-ND ")
        (field (name "MANPARTNO_1") "RC0603JR-0762RL ")
        (field (name "MANUFACTURER_1") "Yaego")
        (field (name "MNT-TYPE") "SM")
        (field (name "NO-PINS") "2")
        (field (name "PACKAGE") "0603 (16080 Metric)")
        (field (name "TOLERANCE") "5%")
      )
      (libsource (lib "eagle-import") (part "RESISTOR--5%-060362"))
    )
    (comp (ref "R19")
      (value "62")
      (footprint "eagle-import:0603_1608METRIC")
      (description "RES 62 OHM 1/10W 5% 0603 SMD")
      (fields
        (field (name "DISTRIBUTORPARTNO") "311-62GRCT-ND ")
        (field (name "MANPARTNO") "RC0603JR-0762RL ")
        (field (name "MANUFACTURER") "Yaego")
        (field (name "DISTRIBUTOR") "Digikey")
        (field (name "DISTRIBUTORPARTNO_1") "311-62GRCT-ND ")
        (field (name "MANPARTNO_1") "RC0603JR-0762RL ")
        (field (name "MANUFACTURER_1") "Yaego")
        (field (name "MNT-TYPE") "SM")
        (field (name "NO-PINS") "2")
        (field (name "PACKAGE") "0603 (16080 Metric)")
        (field (name "TOLERANCE") "5%")
      )
      (libsource (lib "eagle-import") (part "RESISTOR--5%-060362"))
    )
    (comp (ref "R20")
      (value "62")
      (footprint "eagle-import:0603_1608METRIC")
      (description "RES 62 OHM 1/10W 5% 0603 SMD")
      (fields
        (field (name "DISTRIBUTORPARTNO") "311-62GRCT-ND ")
        (field (name "MANPARTNO") "RC0603JR-0762RL ")
        (field (name "MANUFACTURER") "Yaego")
        (field (name "DISTRIBUTOR") "Digikey")
        (field (name "DISTRIBUTORPARTNO_1") "311-62GRCT-ND ")
        (field (name "MANPARTNO_1") "RC0603JR-0762RL ")
        (field (name "MANUFACTURER_1") "Yaego")
        (field (name "MNT-TYPE") "SM")
        (field (name "NO-PINS") "2")
        (field (name "PACKAGE") "0603 (16080 Metric)")
        (field (name "TOLERANCE") "5%")
      )
      (libsource (lib "eagle-import") (part "RESISTOR--5%-060362"))
    )
    (comp (ref "R21")
      (value "62")
      (footprint "eagle-import:0603_1608METRIC")
      (description "RES 62 OHM 1/10W 5% 0603 SMD")
      (fields
        (field (name "DISTRIBUTORPARTNO") "311-62GRCT-ND ")
        (field (name "MANPARTNO") "RC0603JR-0762RL ")
        (field (name "MANUFACTURER") "Yaego")
        (field (name "DISTRIBUTOR") "Digikey")
        (field (name "DISTRIBUTORPARTNO_1") "311-62GRCT-ND ")
        (field (name "MANPARTNO_1") "RC0603JR-0762RL ")
        (field (name "MANUFACTURER_1") "Yaego")
        (field (name "MNT-TYPE") "SM")
        (field (name "NO-PINS") "2")
        (field (name "PACKAGE") "0603 (16080 Metric)")
        (field (name "TOLERANCE") "5%")
      )
      (libsource (lib "eagle-import") (part "RESISTOR--5%-060362"))
    )
    (comp (ref "R22")
      (value "62")
      (footprint "eagle-import:0603_1608METRIC")
      (description "RES 62 OHM 1/10W 5% 0603 SMD")
      (fields
        (field (name "DISTRIBUTORPARTNO") "311-62GRCT-ND ")
        (field (name "MANPARTNO") "RC0603JR-0762RL ")
        (field (name "MANUFACTURER") "Yaego")
        (field (name "DISTRIBUTOR") "Digikey")
        (field (name "DISTRIBUTORPARTNO_1") "311-62GRCT-ND ")
        (field (name "MANPARTNO_1") "RC0603JR-0762RL ")
        (field (name "MANUFACTURER_1") "Yaego")
        (field (name "MNT-TYPE") "SM")
        (field (name "NO-PINS") "2")
        (field (name "PACKAGE") "0603 (16080 Metric)")
        (field (name "TOLERANCE") "5%")
      )
      (libsource (lib "eagle-import") (part "RESISTOR--5%-060362"))
    )
    (comp (ref "R23")
      (value "62")
      (footprint "eagle-import:0603_1608METRIC")
      (description "RES 62 OHM 1/10W 5% 0603 SMD")
      (fields
        (field (name "DISTRIBUTORPARTNO") "311-62GRCT-ND ")
        (field (name "MANPARTNO") "RC0603JR-0762RL ")
        (field (name "MANUFACTURER") "Yaego")
        (field (name "DISTRIBUTOR") "Digikey")
        (field (name "DISTRIBUTORPARTNO_1") "311-62GRCT-ND ")
        (field (name "MANPARTNO_1") "RC0603JR-0762RL ")
        (field (name "MANUFACTURER_1") "Yaego")
        (field (name "MNT-TYPE") "SM")
        (field (name "NO-PINS") "2")
        (field (name "PACKAGE") "0603 (16080 Metric)")
        (field (name "TOLERANCE") "5%")
      )
      (libsource (lib "eagle-import") (part "RESISTOR--5%-060362"))
    )
    (comp (ref "R24")
      (value "62")
      (footprint "eagle-import:0603_1608METRIC")
      (description "RES 62 OHM 1/10W 5% 0603 SMD")
      (fields
        (field (name "DISTRIBUTORPARTNO") "311-62GRCT-ND ")
        (field (name "MANPARTNO") "RC0603JR-0762RL ")
        (field (name "MANUFACTURER") "Yaego")
        (field (name "DISTRIBUTOR") "Digikey")
        (field (name "DISTRIBUTORPARTNO_1") "311-62GRCT-ND ")
        (field (name "MANPARTNO_1") "RC0603JR-0762RL ")
        (field (name "MANUFACTURER_1") "Yaego")
        (field (name "MNT-TYPE") "SM")
        (field (name "NO-PINS") "2")
        (field (name "PACKAGE") "0603 (16080 Metric)")
        (field (name "TOLERANCE") "5%")
      )
      (libsource (lib "eagle-import") (part "RESISTOR--5%-060362"))
    )
    (comp (ref "R25")
      (value "62")
      (footprint "eagle-import:0603_1608METRIC")
      (description "RES 62 OHM 1/10W 5% 0603 SMD")
      (fields
        (field (name "DISTRIBUTORPARTNO") "311-62GRCT-ND ")
        (field (name "MANPARTNO") "RC0603JR-0762RL ")
        (field (name "MANUFACTURER") "Yaego")
        (field (name "DISTRIBUTOR") "Digikey")
        (field (name "DISTRIBUTORPARTNO_1") "311-62GRCT-ND ")
        (field (name "MANPARTNO_1") "RC0603JR-0762RL ")
        (field (name "MANUFACTURER_1") "Yaego")
        (field (name "MNT-TYPE") "SM")
        (field (name "NO-PINS") "2")
        (field (name "PACKAGE") "0603 (16080 Metric)")
        (field (name "TOLERANCE") "5%")
      )
      (libsource (lib "eagle-import") (part "RESISTOR--5%-060362"))
    )
    (comp (ref "R26")
      (value "62")
      (footprint "eagle-import:0603_1608METRIC")
      (description "RES 62 OHM 1/10W 5% 0603 SMD")
      (fields
        (field (name "DISTRIBUTORPARTNO") "311-62GRCT-ND ")
        (field (name "MANPARTNO") "RC0603JR-0762RL ")
        (field (name "MANUFACTURER") "Yaego")
        (field (name "DISTRIBUTOR") "Digikey")
        (field (name "DISTRIBUTORPARTNO_1") "311-62GRCT-ND ")
        (field (name "MANPARTNO_1") "RC0603JR-0762RL ")
        (field (name "MANUFACTURER_1") "Yaego")
        (field (name "MNT-TYPE") "SM")
        (field (name "NO-PINS") "2")
        (field (name "PACKAGE") "0603 (16080 Metric)")
        (field (name "TOLERANCE") "5%")
      )
      (libsource (lib "eagle-import") (part "RESISTOR--5%-060362"))
    )
    (comp (ref "R27")
      (value "62")
      (footprint "eagle-import:0603_1608METRIC")
      (description "RES 62 OHM 1/10W 5% 0603 SMD")
      (fields
        (field (name "DISTRIBUTORPARTNO") "311-62GRCT-ND ")
        (field (name "MANPARTNO") "RC0603JR-0762RL ")
        (field (name "MANUFACTURER") "Yaego")
        (field (name "DISTRIBUTOR") "Digikey")
        (field (name "DISTRIBUTORPARTNO_1") "311-62GRCT-ND ")
        (field (name "MANPARTNO_1") "RC0603JR-0762RL ")
        (field (name "MANUFACTURER_1") "Yaego")
        (field (name "MNT-TYPE") "SM")
        (field (name "NO-PINS") "2")
        (field (name "PACKAGE") "0603 (16080 Metric)")
        (field (name "TOLERANCE") "5%")
      )
      (libsource (lib "eagle-import") (part "RESISTOR--5%-060362"))
    )
    (comp (ref "R28")
      (value "62")
      (footprint "eagle-import:0603_1608METRIC")
      (description "RES 62 OHM 1/10W 5% 0603 SMD")
      (fields
        (field (name "DISTRIBUTORPARTNO") "311-62GRCT-ND ")
        (field (name "MANPARTNO") "RC0603JR-0762RL ")
        (field (name "MANUFACTURER") "Yaego")
        (field (name "DISTRIBUTOR") "Digikey")
        (field (name "DISTRIBUTORPARTNO_1") "311-62GRCT-ND ")
        (field (name "MANPARTNO_1") "RC0603JR-0762RL ")
        (field (name "MANUFACTURER_1") "Yaego")
        (field (name "MNT-TYPE") "SM")
        (field (name "NO-PINS") "2")
        (field (name "PACKAGE") "0603 (16080 Metric)")
        (field (name "TOLERANCE") "5%")
      )
      (libsource (lib "eagle-import") (part "RESISTOR--5%-060362"))
    )
    (comp (ref "R29")
      (value "62")
      (footprint "eagle-import:0603_1608METRIC")
      (description "RES 62 OHM 1/10W 5% 0603 SMD")
      (fields
        (field (name "DISTRIBUTORPARTNO") "311-62GRCT-ND ")
        (field (name "MANPARTNO") "RC0603JR-0762RL ")
        (field (name "MANUFACTURER") "Yaego")
        (field (name "DISTRIBUTOR") "Digikey")
        (field (name "DISTRIBUTORPARTNO_1") "311-62GRCT-ND ")
        (field (name "MANPARTNO_1") "RC0603JR-0762RL ")
        (field (name "MANUFACTURER_1") "Yaego")
        (field (name "MNT-TYPE") "SM")
        (field (name "NO-PINS") "2")
        (field (name "PACKAGE") "0603 (16080 Metric)")
        (field (name "TOLERANCE") "5%")
      )
      (libsource (lib "eagle-import") (part "RESISTOR--5%-060362"))
    )
    (comp (ref "R30")
      (value "62")
      (footprint "eagle-import:0603_1608METRIC")
      (description "RES 62 OHM 1/10W 5% 0603 SMD")
      (fields
        (field (name "DISTRIBUTORPARTNO") "311-62GRCT-ND ")
        (field (name "MANPARTNO") "RC0603JR-0762RL ")
        (field (name "MANUFACTURER") "Yaego")
        (field (name "DISTRIBUTOR") "Digikey")
        (field (name "DISTRIBUTORPARTNO_1") "311-62GRCT-ND ")
        (field (name "MANPARTNO_1") "RC0603JR-0762RL ")
        (field (name "MANUFACTURER_1") "Yaego")
        (field (name "MNT-TYPE") "SM")
        (field (name "NO-PINS") "2")
        (field (name "PACKAGE") "0603 (16080 Metric)")
        (field (name "TOLERANCE") "5%")
      )
      (libsource (lib "eagle-import") (part "RESISTOR--5%-060362"))
    )
    (comp (ref "R31")
      (value "62")
      (footprint "eagle-import:0603_1608METRIC")
      (description "RES 62 OHM 1/10W 5% 0603 SMD")
      (fields
        (field (name "DISTRIBUTORPARTNO") "311-62GRCT-ND ")
        (field (name "MANPARTNO") "RC0603JR-0762RL ")
        (field (name "MANUFACTURER") "Yaego")
        (field (name "DISTRIBUTOR") "Digikey")
        (field (name "DISTRIBUTORPARTNO_1") "311-62GRCT-ND ")
        (field (name "MANPARTNO_1") "RC0603JR-0762RL ")
        (field (name "MANUFACTURER_1") "Yaego")
        (field (name "MNT-TYPE") "SM")
        (field (name "NO-PINS") "2")
        (field (name "PACKAGE") "0603 (16080 Metric)")
        (field (name "TOLERANCE") "5%")
      )
      (libsource (lib "eagle-import") (part "RESISTOR--5%-060362"))
    )
    (comp (ref "R32")
      (value "62")
      (footprint "eagle-import:0603_1608METRIC")
      (description "RES 62 OHM 1/10W 5% 0603 SMD")
      (fields
        (field (name "DISTRIBUTORPARTNO") "311-62GRCT-ND ")
        (field (name "MANPARTNO") "RC0603JR-0762RL ")
        (field (name "MANUFACTURER") "Yaego")
        (field (name "DISTRIBUTOR") "Digikey")
        (field (name "DISTRIBUTORPARTNO_1") "311-62GRCT-ND ")
        (field (name "MANPARTNO_1") "RC0603JR-0762RL ")
        (field (name "MANUFACTURER_1") "Yaego")
        (field (name "MNT-TYPE") "SM")
        (field (name "NO-PINS") "2")
        (field (name "PACKAGE") "0603 (16080 Metric)")
        (field (name "TOLERANCE") "5%")
      )
      (libsource (lib "eagle-import") (part "RESISTOR--5%-060362"))
    )
    (comp (ref "R33")
      (value "62")
      (footprint "eagle-import:0603_1608METRIC")
      (description "RES 62 OHM 1/10W 5% 0603 SMD")
      (fields
        (field (name "DISTRIBUTORPARTNO") "311-62GRCT-ND ")
        (field (name "MANPARTNO") "RC0603JR-0762RL ")
        (field (name "MANUFACTURER") "Yaego")
        (field (name "DISTRIBUTOR") "Digikey")
        (field (name "DISTRIBUTORPARTNO_1") "311-62GRCT-ND ")
        (field (name "MANPARTNO_1") "RC0603JR-0762RL ")
        (field (name "MANUFACTURER_1") "Yaego")
        (field (name "MNT-TYPE") "SM")
        (field (name "NO-PINS") "2")
        (field (name "PACKAGE") "0603 (16080 Metric)")
        (field (name "TOLERANCE") "5%")
      )
      (libsource (lib "eagle-import") (part "RESISTOR--5%-060362"))
    )
    (comp (ref "R34")
      (value "62")
      (footprint "eagle-import:0603_1608METRIC")
      (description "RES 62 OHM 1/10W 5% 0603 SMD")
      (fields
        (field (name "DISTRIBUTORPARTNO") "311-62GRCT-ND ")
        (field (name "MANPARTNO") "RC0603JR-0762RL ")
        (field (name "MANUFACTURER") "Yaego")
        (field (name "DISTRIBUTOR") "Digikey")
        (field (name "DISTRIBUTORPARTNO_1") "311-62GRCT-ND ")
        (field (name "MANPARTNO_1") "RC0603JR-0762RL ")
        (field (name "MANUFACTURER_1") "Yaego")
        (field (name "MNT-TYPE") "SM")
        (field (name "NO-PINS") "2")
        (field (name "PACKAGE") "0603 (16080 Metric)")
        (field (name "TOLERANCE") "5%")
      )
      (libsource (lib "eagle-import") (part "RESISTOR--5%-060362"))
    )
    (comp (ref "R35")
      (value "62")
      (footprint "eagle-import:0603_1608METRIC")
      (description "RES 62 OHM 1/10W 5% 0603 SMD")
      (fields
        (field (name "DISTRIBUTORPARTNO") "311-62GRCT-ND ")
        (field (name "MANPARTNO") "RC0603JR-0762RL ")
        (field (name "MANUFACTURER") "Yaego")
        (field (name "DISTRIBUTOR") "Digikey")
        (field (name "DISTRIBUTORPARTNO_1") "311-62GRCT-ND ")
        (field (name "MANPARTNO_1") "RC0603JR-0762RL ")
        (field (name "MANUFACTURER_1") "Yaego")
        (field (name "MNT-TYPE") "SM")
        (field (name "NO-PINS") "2")
        (field (name "PACKAGE") "0603 (16080 Metric)")
        (field (name "TOLERANCE") "5%")
      )
      (libsource (lib "eagle-import") (part "RESISTOR--5%-060362"))
    )
    (comp (ref "R36")
      (value "62")
      (footprint "eagle-import:0603_1608METRIC")
      (description "RES 62 OHM 1/10W 5% 0603 SMD")
      (fields
        (field (name "DISTRIBUTORPARTNO") "311-62GRCT-ND ")
        (field (name "MANPARTNO") "RC0603JR-0762RL ")
        (field (name "MANUFACTURER") "Yaego")
        (field (name "DISTRIBUTOR") "Digikey")
        (field (name "DISTRIBUTORPARTNO_1") "311-62GRCT-ND ")
        (field (name "MANPARTNO_1") "RC0603JR-0762RL ")
        (field (name "MANUFACTURER_1") "Yaego")
        (field (name "MNT-TYPE") "SM")
        (field (name "NO-PINS") "2")
        (field (name "PACKAGE") "0603 (16080 Metric)")
        (field (name "TOLERANCE") "5%")
      )
      (libsource (lib "eagle-import") (part "RESISTOR--5%-060362"))
    )
    (comp (ref "R37")
      (value "62")
      (footprint "eagle-import:0603_1608METRIC")
      (description "RES 62 OHM 1/10W 5% 0603 SMD")
      (fields
        (field (name "DISTRIBUTORPARTNO") "311-62GRCT-ND ")
        (field (name "MANPARTNO") "RC0603JR-0762RL ")
        (field (name "MANUFACTURER") "Yaego")
        (field (name "DISTRIBUTOR") "Digikey")
        (field (name "DISTRIBUTORPARTNO_1") "311-62GRCT-ND ")
        (field (name "MANPARTNO_1") "RC0603JR-0762RL ")
        (field (name "MANUFACTURER_1") "Yaego")
        (field (name "MNT-TYPE") "SM")
        (field (name "NO-PINS") "2")
        (field (name "PACKAGE") "0603 (16080 Metric)")
        (field (name "TOLERANCE") "5%")
      )
      (libsource (lib "eagle-import") (part "RESISTOR--5%-060362"))
    )
    (comp (ref "R38")
      (value "62")
      (footprint "eagle-import:0603_1608METRIC")
      (description "RES 62 OHM 1/10W 5% 0603 SMD")
      (fields
        (field (name "DISTRIBUTORPARTNO") "311-62GRCT-ND ")
        (field (name "MANPARTNO") "RC0603JR-0762RL ")
        (field (name "MANUFACTURER") "Yaego")
        (field (name "DISTRIBUTOR") "Digikey")
        (field (name "DISTRIBUTORPARTNO_1") "311-62GRCT-ND ")
        (field (name "MANPARTNO_1") "RC0603JR-0762RL ")
        (field (name "MANUFACTURER_1") "Yaego")
        (field (name "MNT-TYPE") "SM")
        (field (name "NO-PINS") "2")
        (field (name "PACKAGE") "0603 (16080 Metric)")
        (field (name "TOLERANCE") "5%")
      )
      (libsource (lib "eagle-import") (part "RESISTOR--5%-060362"))
    )
    (comp (ref "R39")
      (value "62")
      (footprint "eagle-import:0603_1608METRIC")
      (description "RES 62 OHM 1/10W 5% 0603 SMD")
      (fields
        (field (name "DISTRIBUTORPARTNO") "311-62GRCT-ND ")
        (field (name "MANPARTNO") "RC0603JR-0762RL ")
        (field (name "MANUFACTURER") "Yaego")
        (field (name "DISTRIBUTOR") "Digikey")
        (field (name "DISTRIBUTORPARTNO_1") "311-62GRCT-ND ")
        (field (name "MANPARTNO_1") "RC0603JR-0762RL ")
        (field (name "MANUFACTURER_1") "Yaego")
        (field (name "MNT-TYPE") "SM")
        (field (name "NO-PINS") "2")
        (field (name "PACKAGE") "0603 (16080 Metric)")
        (field (name "TOLERANCE") "5%")
      )
      (libsource (lib "eagle-import") (part "RESISTOR--5%-060362"))
    )
    (comp (ref "R40")
      (value "62")
      (footprint "eagle-import:0603_1608METRIC")
      (description "RES 62 OHM 1/10W 5% 0603 SMD")
      (fields
        (field (name "DISTRIBUTORPARTNO") "311-62GRCT-ND ")
        (field (name "MANPARTNO") "RC0603JR-0762RL ")
        (field (name "MANUFACTURER") "Yaego")
        (field (name "DISTRIBUTOR") "Digikey")
        (field (name "DISTRIBUTORPARTNO_1") "311-62GRCT-ND ")
        (field (name "MANPARTNO_1") "RC0603JR-0762RL ")
        (field (name "MANUFACTURER_1") "Yaego")
        (field (name "MNT-TYPE") "SM")
        (field (name "NO-PINS") "2")
        (field (name "PACKAGE") "0603 (16080 Metric)")
        (field (name "TOLERANCE") "5%")
      )
      (libsource (lib "eagle-import") (part "RESISTOR--5%-060362"))
    )
    (comp (ref "R41")
      (value "62")
      (footprint "eagle-import:0603_1608METRIC")
      (description "RES 62 OHM 1/10W 5% 0603 SMD")
      (fields
        (field (name "DISTRIBUTORPARTNO") "311-62GRCT-ND ")
        (field (name "MANPARTNO") "RC0603JR-0762RL ")
        (field (name "MANUFACTURER") "Yaego")
        (field (name "DISTRIBUTOR") "Digikey")
        (field (name "DISTRIBUTORPARTNO_1") "311-62GRCT-ND ")
        (field (name "MANPARTNO_1") "RC0603JR-0762RL ")
        (field (name "MANUFACTURER_1") "Yaego")
        (field (name "MNT-TYPE") "SM")
        (field (name "NO-PINS") "2")
        (field (name "PACKAGE") "0603 (16080 Metric)")
        (field (name "TOLERANCE") "5%")
      )
      (libsource (lib "eagle-import") (part "RESISTOR--5%-060362"))
    )
    (comp (ref "R42")
      (value "62")
      (footprint "eagle-import:0603_1608METRIC")
      (description "RES 62 OHM 1/10W 5% 0603 SMD")
      (fields
        (field (name "DISTRIBUTORPARTNO") "311-62GRCT-ND ")
        (field (name "MANPARTNO") "RC0603JR-0762RL ")
        (field (name "MANUFACTURER") "Yaego")
        (field (name "DISTRIBUTOR") "Digikey")
        (field (name "DISTRIBUTORPARTNO_1") "311-62GRCT-ND ")
        (field (name "MANPARTNO_1") "RC0603JR-0762RL ")
        (field (name "MANUFACTURER_1") "Yaego")
        (field (name "MNT-TYPE") "SM")
        (field (name "NO-PINS") "2")
        (field (name "PACKAGE") "0603 (16080 Metric)")
        (field (name "TOLERANCE") "5%")
      )
      (libsource (lib "eagle-import") (part "RESISTOR--5%-060362"))
    )
    (comp (ref "R43")
      (value "62")
      (footprint "eagle-import:0603_1608METRIC")
      (description "RES 62 OHM 1/10W 5% 0603 SMD")
      (fields
        (field (name "DISTRIBUTORPARTNO") "311-62GRCT-ND ")
        (field (name "MANPARTNO") "RC0603JR-0762RL ")
        (field (name "MANUFACTURER") "Yaego")
        (field (name "DISTRIBUTOR") "Digikey")
        (field (name "DISTRIBUTORPARTNO_1") "311-62GRCT-ND ")
        (field (name "MANPARTNO_1") "RC0603JR-0762RL ")
        (field (name "MANUFACTURER_1") "Yaego")
        (field (name "MNT-TYPE") "SM")
        (field (name "NO-PINS") "2")
        (field (name "PACKAGE") "0603 (16080 Metric)")
        (field (name "TOLERANCE") "5%")
      )
      (libsource (lib "eagle-import") (part "RESISTOR--5%-060362"))
    )
    (comp (ref "R44")
      (value "62")
      (footprint "eagle-import:0603_1608METRIC")
      (description "RES 62 OHM 1/10W 5% 0603 SMD")
      (fields
        (field (name "DISTRIBUTORPARTNO") "311-62GRCT-ND ")
        (field (name "MANPARTNO") "RC0603JR-0762RL ")
        (field (name "MANUFACTURER") "Yaego")
        (field (name "DISTRIBUTOR") "Digikey")
        (field (name "DISTRIBUTORPARTNO_1") "311-62GRCT-ND ")
        (field (name "MANPARTNO_1") "RC0603JR-0762RL ")
        (field (name "MANUFACTURER_1") "Yaego")
        (field (name "MNT-TYPE") "SM")
        (field (name "NO-PINS") "2")
        (field (name "PACKAGE") "0603 (16080 Metric)")
        (field (name "TOLERANCE") "5%")
      )
      (libsource (lib "eagle-import") (part "RESISTOR--5%-060362"))
    )
    (comp (ref "R45")
      (value "62")
      (footprint "eagle-import:0603_1608METRIC")
      (description "RES 62 OHM 1/10W 5% 0603 SMD")
      (fields
        (field (name "DISTRIBUTORPARTNO") "311-62GRCT-ND ")
        (field (name "MANPARTNO") "RC0603JR-0762RL ")
        (field (name "MANUFACTURER") "Yaego")
        (field (name "DISTRIBUTOR") "Digikey")
        (field (name "DISTRIBUTORPARTNO_1") "311-62GRCT-ND ")
        (field (name "MANPARTNO_1") "RC0603JR-0762RL ")
        (field (name "MANUFACTURER_1") "Yaego")
        (field (name "MNT-TYPE") "SM")
        (field (name "NO-PINS") "2")
        (field (name "PACKAGE") "0603 (16080 Metric)")
        (field (name "TOLERANCE") "5%")
      )
      (libsource (lib "eagle-import") (part "RESISTOR--5%-060362"))
    )
    (comp (ref "R46")
      (value "62")
      (footprint "eagle-import:0603_1608METRIC")
      (description "RES 62 OHM 1/10W 5% 0603 SMD")
      (fields
        (field (name "DISTRIBUTORPARTNO") "311-62GRCT-ND ")
        (field (name "MANPARTNO") "RC0603JR-0762RL ")
        (field (name "MANUFACTURER") "Yaego")
        (field (name "DISTRIBUTOR") "Digikey")
        (field (name "DISTRIBUTORPARTNO_1") "311-62GRCT-ND ")
        (field (name "MANPARTNO_1") "RC0603JR-0762RL ")
        (field (name "MANUFACTURER_1") "Yaego")
        (field (name "MNT-TYPE") "SM")
        (field (name "NO-PINS") "2")
        (field (name "PACKAGE") "0603 (16080 Metric)")
        (field (name "TOLERANCE") "5%")
      )
      (libsource (lib "eagle-import") (part "RESISTOR--5%-060362"))
    )
    (comp (ref "R47")
      (value "62")
      (footprint "eagle-import:0603_1608METRIC")
      (description "RES 62 OHM 1/10W 5% 0603 SMD")
      (fields
        (field (name "DISTRIBUTORPARTNO") "311-62GRCT-ND ")
        (field (name "MANPARTNO") "RC0603JR-0762RL ")
        (field (name "MANUFACTURER") "Yaego")
        (field (name "DISTRIBUTOR") "Digikey")
        (field (name "DISTRIBUTORPARTNO_1") "311-62GRCT-ND ")
        (field (name "MANPARTNO_1") "RC0603JR-0762RL ")
        (field (name "MANUFACTURER_1") "Yaego")
        (field (name "MNT-TYPE") "SM")
        (field (name "NO-PINS") "2")
        (field (name "PACKAGE") "0603 (16080 Metric)")
        (field (name "TOLERANCE") "5%")
      )
      (libsource (lib "eagle-import") (part "RESISTOR--5%-060362"))
    )
    (comp (ref "R48")
      (value "62")
      (footprint "eagle-import:0603_1608METRIC")
      (description "RES 62 OHM 1/10W 5% 0603 SMD")
      (fields
        (field (name "DISTRIBUTORPARTNO") "311-62GRCT-ND ")
        (field (name "MANPARTNO") "RC0603JR-0762RL ")
        (field (name "MANUFACTURER") "Yaego")
        (field (name "DISTRIBUTOR") "Digikey")
        (field (name "DISTRIBUTORPARTNO_1") "311-62GRCT-ND ")
        (field (name "MANPARTNO_1") "RC0603JR-0762RL ")
        (field (name "MANUFACTURER_1") "Yaego")
        (field (name "MNT-TYPE") "SM")
        (field (name "NO-PINS") "2")
        (field (name "PACKAGE") "0603 (16080 Metric)")
        (field (name "TOLERANCE") "5%")
      )
      (libsource (lib "eagle-import") (part "RESISTOR--5%-060362"))
    )
    (comp (ref "R49")
      (value "2k")
      (footprint "eagle-import:0603_1608METRIC")
      (fields
        (field (name "DISTRIBUTORPARTNO") "311-2.0KGRCT-ND")
        (field (name "MANPARTNO") "RC0603JR-072KL")
        (field (name "MANUFACTURER") "Yaego")
      )
      (libsource (lib "eagle-import") (part "RESISTOR--5%-06032K"))
    )
    (comp (ref "R50")
      (value "2k")
      (footprint "eagle-import:0603_1608METRIC")
      (fields
        (field (name "DISTRIBUTORPARTNO") "311-2.0KGRCT-ND")
        (field (name "MANPARTNO") "RC0603JR-072KL")
        (field (name "MANUFACTURER") "Yaego")
      )
      (libsource (lib "eagle-import") (part "RESISTOR--5%-06032K"))
    )
    (comp (ref "R51")
      (value "47k")
      (footprint "eagle-import:0603_1608METRIC")
      (fields
        (field (name "DISTRIBUTORPARTNO") "311-47KGRCT-ND")
        (field (name "MANPARTNO") "RC0603JR-0747KL")
        (field (name "MANUFACTURER") "Yaego")
      )
      (libsource (lib "eagle-import") (part "RESISTOR--5%-060347K"))
    )
    (comp (ref "R52")
      (value "2k")
      (footprint "eagle-import:0603_1608METRIC")
      (fields
        (field (name "DISTRIBUTORPARTNO") "311-2.0KGRCT-ND")
        (field (name "MANPARTNO") "RC0603JR-072KL")
        (field (name "MANUFACTURER") "Yaego")
      )
      (libsource (lib "eagle-import") (part "RESISTOR--5%-06032K"))
    )
    (comp (ref "R53")
      (value "2k")
      (footprint "eagle-import:0603_1608METRIC")
      (fields
        (field (name "DISTRIBUTORPARTNO") "311-2.0KGRCT-ND")
        (field (name "MANPARTNO") "RC0603JR-072KL")
        (field (name "MANUFACTURER") "Yaego")
      )
      (libsource (lib "eagle-import") (part "RESISTOR--5%-06032K"))
    )
    (comp (ref "R54")
      (value "10k")
      (footprint "eagle-import:0603_1608METRIC")
      (fields
        (field (name "DISTRIBUTORPARTNO") "311-10KGRCT-ND")
        (field (name "MANPARTNO") "RC0603JR-0710KL")
        (field (name "MANUFACTURER") "Yaego")
      )
      (libsource (lib "eagle-import") (part "RESISTOR--5%-060310K"))
    )
    (comp (ref "R55")
      (value "4.7k")
      (footprint "eagle-import:0603_1608METRIC")
      (fields
        (field (name "DISTRIBUTORPARTNO") "311-4.7kGRCT-ND")
        (field (name "MANPARTNO") "RC0603JR-074K7L")
        (field (name "MANUFACTURER") "Yaego")
      )
      (libsource (lib "eagle-import") (part "RESISTOR--5%-06034.7K"))
    )
    (comp (ref "R56")
      (value "2k")
      (footprint "eagle-import:0603_1608METRIC")
      (fields
        (field (name "DISTRIBUTORPARTNO") "311-2.0KGRCT-ND")
        (field (name "MANPARTNO") "RC0603JR-072KL")
        (field (name "MANUFACTURER") "Yaego")
      )
      (libsource (lib "eagle-import") (part "RESISTOR--5%-06032K"))
    )
    (comp (ref "R57")
      (value "62")
      (footprint "eagle-import:0603_1608METRIC")
      (description "RES 62 OHM 1/10W 5% 0603 SMD")
      (fields
        (field (name "DISTRIBUTORPARTNO") "311-62GRCT-ND ")
        (field (name "MANPARTNO") "RC0603JR-0762RL ")
        (field (name "MANUFACTURER") "Yaego")
        (field (name "DISTRIBUTOR") "Digikey")
        (field (name "DISTRIBUTORPARTNO_1") "311-62GRCT-ND ")
        (field (name "MANPARTNO_1") "RC0603JR-0762RL ")
        (field (name "MANUFACTURER_1") "Yaego")
        (field (name "MNT-TYPE") "SM")
        (field (name "NO-PINS") "2")
        (field (name "PACKAGE") "0603 (16080 Metric)")
        (field (name "TOLERANCE") "5%")
      )
      (libsource (lib "eagle-import") (part "RESISTOR--5%-060362"))
    )
    (comp (ref "R58")
      (value "62")
      (footprint "eagle-import:0603_1608METRIC")
      (description "RES 62 OHM 1/10W 5% 0603 SMD")
      (fields
        (field (name "DISTRIBUTORPARTNO") "311-62GRCT-ND ")
        (field (name "MANPARTNO") "RC0603JR-0762RL ")
        (field (name "MANUFACTURER") "Yaego")
        (field (name "DISTRIBUTOR") "Digikey")
        (field (name "DISTRIBUTORPARTNO_1") "311-62GRCT-ND ")
        (field (name "MANPARTNO_1") "RC0603JR-0762RL ")
        (field (name "MANUFACTURER_1") "Yaego")
        (field (name "MNT-TYPE") "SM")
        (field (name "NO-PINS") "2")
        (field (name "PACKAGE") "0603 (16080 Metric)")
        (field (name "TOLERANCE") "5%")
      )
      (libsource (lib "eagle-import") (part "RESISTOR--5%-060362"))
    )
    (comp (ref "R59")
      (value "62")
      (footprint "eagle-import:0603_1608METRIC")
      (description "RES 62 OHM 1/10W 5% 0603 SMD")
      (fields
        (field (name "DISTRIBUTORPARTNO") "311-62GRCT-ND ")
        (field (name "MANPARTNO") "RC0603JR-0762RL ")
        (field (name "MANUFACTURER") "Yaego")
        (field (name "DISTRIBUTOR") "Digikey")
        (field (name "DISTRIBUTORPARTNO_1") "311-62GRCT-ND ")
        (field (name "MANPARTNO_1") "RC0603JR-0762RL ")
        (field (name "MANUFACTURER_1") "Yaego")
        (field (name "MNT-TYPE") "SM")
        (field (name "NO-PINS") "2")
        (field (name "PACKAGE") "0603 (16080 Metric)")
        (field (name "TOLERANCE") "5%")
      )
      (libsource (lib "eagle-import") (part "RESISTOR--5%-060362"))
    )
    (comp (ref "R60")
      (value "62")
      (footprint "eagle-import:0603_1608METRIC")
      (description "RES 62 OHM 1/10W 5% 0603 SMD")
      (fields
        (field (name "DISTRIBUTORPARTNO") "311-62GRCT-ND ")
        (field (name "MANPARTNO") "RC0603JR-0762RL ")
        (field (name "MANUFACTURER") "Yaego")
        (field (name "DISTRIBUTOR") "Digikey")
        (field (name "DISTRIBUTORPARTNO_1") "311-62GRCT-ND ")
        (field (name "MANPARTNO_1") "RC0603JR-0762RL ")
        (field (name "MANUFACTURER_1") "Yaego")
        (field (name "MNT-TYPE") "SM")
        (field (name "NO-PINS") "2")
        (field (name "PACKAGE") "0603 (16080 Metric)")
        (field (name "TOLERANCE") "5%")
      )
      (libsource (lib "eagle-import") (part "RESISTOR--5%-060362"))
    )
    (comp (ref "R61")
      (value "62")
      (footprint "eagle-import:0603_1608METRIC")
      (description "RES 62 OHM 1/10W 5% 0603 SMD")
      (fields
        (field (name "DISTRIBUTORPARTNO") "311-62GRCT-ND ")
        (field (name "MANPARTNO") "RC0603JR-0762RL ")
        (field (name "MANUFACTURER") "Yaego")
        (field (name "DISTRIBUTOR") "Digikey")
        (field (name "DISTRIBUTORPARTNO_1") "311-62GRCT-ND ")
        (field (name "MANPARTNO_1") "RC0603JR-0762RL ")
        (field (name "MANUFACTURER_1") "Yaego")
        (field (name "MNT-TYPE") "SM")
        (field (name "NO-PINS") "2")
        (field (name "PACKAGE") "0603 (16080 Metric)")
        (field (name "TOLERANCE") "5%")
      )
      (libsource (lib "eagle-import") (part "RESISTOR--5%-060362"))
    )
    (comp (ref "R62")
      (value "62")
      (footprint "eagle-import:0603_1608METRIC")
      (description "RES 62 OHM 1/10W 5% 0603 SMD")
      (fields
        (field (name "DISTRIBUTORPARTNO") "311-62GRCT-ND ")
        (field (name "MANPARTNO") "RC0603JR-0762RL ")
        (field (name "MANUFACTURER") "Yaego")
        (field (name "DISTRIBUTOR") "Digikey")
        (field (name "DISTRIBUTORPARTNO_1") "311-62GRCT-ND ")
        (field (name "MANPARTNO_1") "RC0603JR-0762RL ")
        (field (name "MANUFACTURER_1") "Yaego")
        (field (name "MNT-TYPE") "SM")
        (field (name "NO-PINS") "2")
        (field (name "PACKAGE") "0603 (16080 Metric)")
        (field (name "TOLERANCE") "5%")
      )
      (libsource (lib "eagle-import") (part "RESISTOR--5%-060362"))
    )
    (comp (ref "R63")
      (value "62")
      (footprint "eagle-import:0603_1608METRIC")
      (description "RES 62 OHM 1/10W 5% 0603 SMD")
      (fields
        (field (name "DISTRIBUTORPARTNO") "311-62GRCT-ND ")
        (field (name "MANPARTNO") "RC0603JR-0762RL ")
        (field (name "MANUFACTURER") "Yaego")
        (field (name "DISTRIBUTOR") "Digikey")
        (field (name "DISTRIBUTORPARTNO_1") "311-62GRCT-ND ")
        (field (name "MANPARTNO_1") "RC0603JR-0762RL ")
        (field (name "MANUFACTURER_1") "Yaego")
        (field (name "MNT-TYPE") "SM")
        (field (name "NO-PINS") "2")
        (field (name "PACKAGE") "0603 (16080 Metric)")
        (field (name "TOLERANCE") "5%")
      )
      (libsource (lib "eagle-import") (part "RESISTOR--5%-060362"))
    )
    (comp (ref "R64")
      (value "62")
      (footprint "eagle-import:0603_1608METRIC")
      (description "RES 62 OHM 1/10W 5% 0603 SMD")
      (fields
        (field (name "DISTRIBUTORPARTNO") "311-62GRCT-ND ")
        (field (name "MANPARTNO") "RC0603JR-0762RL ")
        (field (name "MANUFACTURER") "Yaego")
        (field (name "DISTRIBUTOR") "Digikey")
        (field (name "DISTRIBUTORPARTNO_1") "311-62GRCT-ND ")
        (field (name "MANPARTNO_1") "RC0603JR-0762RL ")
        (field (name "MANUFACTURER_1") "Yaego")
        (field (name "MNT-TYPE") "SM")
        (field (name "NO-PINS") "2")
        (field (name "PACKAGE") "0603 (16080 Metric)")
        (field (name "TOLERANCE") "5%")
      )
      (libsource (lib "eagle-import") (part "RESISTOR--5%-060362"))
    )
    (comp (ref "R65")
      (value "62")
      (footprint "eagle-import:0603_1608METRIC")
      (description "RES 62 OHM 1/10W 5% 0603 SMD")
      (fields
        (field (name "DISTRIBUTORPARTNO") "311-62GRCT-ND ")
        (field (name "MANPARTNO") "RC0603JR-0762RL ")
        (field (name "MANUFACTURER") "Yaego")
        (field (name "DISTRIBUTOR") "Digikey")
        (field (name "DISTRIBUTORPARTNO_1") "311-62GRCT-ND ")
        (field (name "MANPARTNO_1") "RC0603JR-0762RL ")
        (field (name "MANUFACTURER_1") "Yaego")
        (field (name "MNT-TYPE") "SM")
        (field (name "NO-PINS") "2")
        (field (name "PACKAGE") "0603 (16080 Metric)")
        (field (name "TOLERANCE") "5%")
      )
      (libsource (lib "eagle-import") (part "RESISTOR--5%-060362"))
    )
    (comp (ref "R66")
      (value "62")
      (footprint "eagle-import:0603_1608METRIC")
      (description "RES 62 OHM 1/10W 5% 0603 SMD")
      (fields
        (field (name "DISTRIBUTORPARTNO") "311-62GRCT-ND ")
        (field (name "MANPARTNO") "RC0603JR-0762RL ")
        (field (name "MANUFACTURER") "Yaego")
        (field (name "DISTRIBUTOR") "Digikey")
        (field (name "DISTRIBUTORPARTNO_1") "311-62GRCT-ND ")
        (field (name "MANPARTNO_1") "RC0603JR-0762RL ")
        (field (name "MANUFACTURER_1") "Yaego")
        (field (name "MNT-TYPE") "SM")
        (field (name "NO-PINS") "2")
        (field (name "PACKAGE") "0603 (16080 Metric)")
        (field (name "TOLERANCE") "5%")
      )
      (libsource (lib "eagle-import") (part "RESISTOR--5%-060362"))
    )
    (comp (ref "R67")
      (value "62")
      (footprint "eagle-import:0603_1608METRIC")
      (description "RES 62 OHM 1/10W 5% 0603 SMD")
      (fields
        (field (name "DISTRIBUTORPARTNO") "311-62GRCT-ND ")
        (field (name "MANPARTNO") "RC0603JR-0762RL ")
        (field (name "MANUFACTURER") "Yaego")
        (field (name "DISTRIBUTOR") "Digikey")
        (field (name "DISTRIBUTORPARTNO_1") "311-62GRCT-ND ")
        (field (name "MANPARTNO_1") "RC0603JR-0762RL ")
        (field (name "MANUFACTURER_1") "Yaego")
        (field (name "MNT-TYPE") "SM")
        (field (name "NO-PINS") "2")
        (field (name "PACKAGE") "0603 (16080 Metric)")
        (field (name "TOLERANCE") "5%")
      )
      (libsource (lib "eagle-import") (part "RESISTOR--5%-060362"))
    )
    (comp (ref "R68")
      (value "62")
      (footprint "eagle-import:0603_1608METRIC")
      (description "RES 62 OHM 1/10W 5% 0603 SMD")
      (fields
        (field (name "DISTRIBUTORPARTNO") "311-62GRCT-ND ")
        (field (name "MANPARTNO") "RC0603JR-0762RL ")
        (field (name "MANUFACTURER") "Yaego")
        (field (name "DISTRIBUTOR") "Digikey")
        (field (name "DISTRIBUTORPARTNO_1") "311-62GRCT-ND ")
        (field (name "MANPARTNO_1") "RC0603JR-0762RL ")
        (field (name "MANUFACTURER_1") "Yaego")
        (field (name "MNT-TYPE") "SM")
        (field (name "NO-PINS") "2")
        (field (name "PACKAGE") "0603 (16080 Metric)")
        (field (name "TOLERANCE") "5%")
      )
      (libsource (lib "eagle-import") (part "RESISTOR--5%-060362"))
    )
    (comp (ref "R69")
      (value "62")
      (footprint "eagle-import:0603_1608METRIC")
      (description "RES 62 OHM 1/10W 5% 0603 SMD")
      (fields
        (field (name "DISTRIBUTORPARTNO") "311-62GRCT-ND ")
        (field (name "MANPARTNO") "RC0603JR-0762RL ")
        (field (name "MANUFACTURER") "Yaego")
        (field (name "DISTRIBUTOR") "Digikey")
        (field (name "DISTRIBUTORPARTNO_1") "311-62GRCT-ND ")
        (field (name "MANPARTNO_1") "RC0603JR-0762RL ")
        (field (name "MANUFACTURER_1") "Yaego")
        (field (name "MNT-TYPE") "SM")
        (field (name "NO-PINS") "2")
        (field (name "PACKAGE") "0603 (16080 Metric)")
        (field (name "TOLERANCE") "5%")
      )
      (libsource (lib "eagle-import") (part "RESISTOR--5%-060362"))
    )
    (comp (ref "R70")
      (value "62")
      (footprint "eagle-import:0603_1608METRIC")
      (description "RES 62 OHM 1/10W 5% 0603 SMD")
      (fields
        (field (name "DISTRIBUTORPARTNO") "311-62GRCT-ND ")
        (field (name "MANPARTNO") "RC0603JR-0762RL ")
        (field (name "MANUFACTURER") "Yaego")
        (field (name "DISTRIBUTOR") "Digikey")
        (field (name "DISTRIBUTORPARTNO_1") "311-62GRCT-ND ")
        (field (name "MANPARTNO_1") "RC0603JR-0762RL ")
        (field (name "MANUFACTURER_1") "Yaego")
        (field (name "MNT-TYPE") "SM")
        (field (name "NO-PINS") "2")
        (field (name "PACKAGE") "0603 (16080 Metric)")
        (field (name "TOLERANCE") "5%")
      )
      (libsource (lib "eagle-import") (part "RESISTOR--5%-060362"))
    )
    (comp (ref "R71")
      (value "62")
      (footprint "eagle-import:0603_1608METRIC")
      (description "RES 62 OHM 1/10W 5% 0603 SMD")
      (fields
        (field (name "DISTRIBUTORPARTNO") "311-62GRCT-ND ")
        (field (name "MANPARTNO") "RC0603JR-0762RL ")
        (field (name "MANUFACTURER") "Yaego")
        (field (name "DISTRIBUTOR") "Digikey")
        (field (name "DISTRIBUTORPARTNO_1") "311-62GRCT-ND ")
        (field (name "MANPARTNO_1") "RC0603JR-0762RL ")
        (field (name "MANUFACTURER_1") "Yaego")
        (field (name "MNT-TYPE") "SM")
        (field (name "NO-PINS") "2")
        (field (name "PACKAGE") "0603 (16080 Metric)")
        (field (name "TOLERANCE") "5%")
      )
      (libsource (lib "eagle-import") (part "RESISTOR--5%-060362"))
    )
    (comp (ref "R72")
      (value "62")
      (footprint "eagle-import:0603_1608METRIC")
      (description "RES 62 OHM 1/10W 5% 0603 SMD")
      (fields
        (field (name "DISTRIBUTORPARTNO") "311-62GRCT-ND ")
        (field (name "MANPARTNO") "RC0603JR-0762RL ")
        (field (name "MANUFACTURER") "Yaego")
        (field (name "DISTRIBUTOR") "Digikey")
        (field (name "DISTRIBUTORPARTNO_1") "311-62GRCT-ND ")
        (field (name "MANPARTNO_1") "RC0603JR-0762RL ")
        (field (name "MANUFACTURER_1") "Yaego")
        (field (name "MNT-TYPE") "SM")
        (field (name "NO-PINS") "2")
        (field (name "PACKAGE") "0603 (16080 Metric)")
        (field (name "TOLERANCE") "5%")
      )
      (libsource (lib "eagle-import") (part "RESISTOR--5%-060362"))
    )
    (comp (ref "R73")
      (value "62")
      (footprint "eagle-import:0603_1608METRIC")
      (description "RES 62 OHM 1/10W 5% 0603 SMD")
      (fields
        (field (name "DISTRIBUTORPARTNO") "311-62GRCT-ND ")
        (field (name "MANPARTNO") "RC0603JR-0762RL ")
        (field (name "MANUFACTURER") "Yaego")
        (field (name "DISTRIBUTOR") "Digikey")
        (field (name "DISTRIBUTORPARTNO_1") "311-62GRCT-ND ")
        (field (name "MANPARTNO_1") "RC0603JR-0762RL ")
        (field (name "MANUFACTURER_1") "Yaego")
        (field (name "MNT-TYPE") "SM")
        (field (name "NO-PINS") "2")
        (field (name "PACKAGE") "0603 (16080 Metric)")
        (field (name "TOLERANCE") "5%")
      )
      (libsource (lib "eagle-import") (part "RESISTOR--5%-060362"))
    )
    (comp (ref "R74")
      (value "62")
      (footprint "eagle-import:0603_1608METRIC")
      (description "RES 62 OHM 1/10W 5% 0603 SMD")
      (fields
        (field (name "DISTRIBUTORPARTNO") "311-62GRCT-ND ")
        (field (name "MANPARTNO") "RC0603JR-0762RL ")
        (field (name "MANUFACTURER") "Yaego")
        (field (name "DISTRIBUTOR") "Digikey")
        (field (name "DISTRIBUTORPARTNO_1") "311-62GRCT-ND ")
        (field (name "MANPARTNO_1") "RC0603JR-0762RL ")
        (field (name "MANUFACTURER_1") "Yaego")
        (field (name "MNT-TYPE") "SM")
        (field (name "NO-PINS") "2")
        (field (name "PACKAGE") "0603 (16080 Metric)")
        (field (name "TOLERANCE") "5%")
      )
      (libsource (lib "eagle-import") (part "RESISTOR--5%-060362"))
    )
    (comp (ref "R75")
      (value "62")
      (footprint "eagle-import:0603_1608METRIC")
      (description "RES 62 OHM 1/10W 5% 0603 SMD")
      (fields
        (field (name "DISTRIBUTORPARTNO") "311-62GRCT-ND ")
        (field (name "MANPARTNO") "RC0603JR-0762RL ")
        (field (name "MANUFACTURER") "Yaego")
        (field (name "DISTRIBUTOR") "Digikey")
        (field (name "DISTRIBUTORPARTNO_1") "311-62GRCT-ND ")
        (field (name "MANPARTNO_1") "RC0603JR-0762RL ")
        (field (name "MANUFACTURER_1") "Yaego")
        (field (name "MNT-TYPE") "SM")
        (field (name "NO-PINS") "2")
        (field (name "PACKAGE") "0603 (16080 Metric)")
        (field (name "TOLERANCE") "5%")
      )
      (libsource (lib "eagle-import") (part "RESISTOR--5%-060362"))
    )
    (comp (ref "R76")
      (value "62")
      (footprint "eagle-import:0603_1608METRIC")
      (description "RES 62 OHM 1/10W 5% 0603 SMD")
      (fields
        (field (name "DISTRIBUTORPARTNO") "311-62GRCT-ND ")
        (field (name "MANPARTNO") "RC0603JR-0762RL ")
        (field (name "MANUFACTURER") "Yaego")
        (field (name "DISTRIBUTOR") "Digikey")
        (field (name "DISTRIBUTORPARTNO_1") "311-62GRCT-ND ")
        (field (name "MANPARTNO_1") "RC0603JR-0762RL ")
        (field (name "MANUFACTURER_1") "Yaego")
        (field (name "MNT-TYPE") "SM")
        (field (name "NO-PINS") "2")
        (field (name "PACKAGE") "0603 (16080 Metric)")
        (field (name "TOLERANCE") "5%")
      )
      (libsource (lib "eagle-import") (part "RESISTOR--5%-060362"))
    )
    (comp (ref "R77")
      (value "62")
      (footprint "eagle-import:0603_1608METRIC")
      (description "RES 62 OHM 1/10W 5% 0603 SMD")
      (fields
        (field (name "DISTRIBUTORPARTNO") "311-62GRCT-ND ")
        (field (name "MANPARTNO") "RC0603JR-0762RL ")
        (field (name "MANUFACTURER") "Yaego")
        (field (name "DISTRIBUTOR") "Digikey")
        (field (name "DISTRIBUTORPARTNO_1") "311-62GRCT-ND ")
        (field (name "MANPARTNO_1") "RC0603JR-0762RL ")
        (field (name "MANUFACTURER_1") "Yaego")
        (field (name "MNT-TYPE") "SM")
        (field (name "NO-PINS") "2")
        (field (name "PACKAGE") "0603 (16080 Metric)")
        (field (name "TOLERANCE") "5%")
      )
      (libsource (lib "eagle-import") (part "RESISTOR--5%-060362"))
    )
    (comp (ref "R78")
      (value "62")
      (footprint "eagle-import:0603_1608METRIC")
      (description "RES 62 OHM 1/10W 5% 0603 SMD")
      (fields
        (field (name "DISTRIBUTORPARTNO") "311-62GRCT-ND ")
        (field (name "MANPARTNO") "RC0603JR-0762RL ")
        (field (name "MANUFACTURER") "Yaego")
        (field (name "DISTRIBUTOR") "Digikey")
        (field (name "DISTRIBUTORPARTNO_1") "311-62GRCT-ND ")
        (field (name "MANPARTNO_1") "RC0603JR-0762RL ")
        (field (name "MANUFACTURER_1") "Yaego")
        (field (name "MNT-TYPE") "SM")
        (field (name "NO-PINS") "2")
        (field (name "PACKAGE") "0603 (16080 Metric)")
        (field (name "TOLERANCE") "5%")
      )
      (libsource (lib "eagle-import") (part "RESISTOR--5%-060362"))
    )
    (comp (ref "R79")
      (value "62")
      (footprint "eagle-import:0603_1608METRIC")
      (description "RES 62 OHM 1/10W 5% 0603 SMD")
      (fields
        (field (name "DISTRIBUTORPARTNO") "311-62GRCT-ND ")
        (field (name "MANPARTNO") "RC0603JR-0762RL ")
        (field (name "MANUFACTURER") "Yaego")
        (field (name "DISTRIBUTOR") "Digikey")
        (field (name "DISTRIBUTORPARTNO_1") "311-62GRCT-ND ")
        (field (name "MANPARTNO_1") "RC0603JR-0762RL ")
        (field (name "MANUFACTURER_1") "Yaego")
        (field (name "MNT-TYPE") "SM")
        (field (name "NO-PINS") "2")
        (field (name "PACKAGE") "0603 (16080 Metric)")
        (field (name "TOLERANCE") "5%")
      )
      (libsource (lib "eagle-import") (part "RESISTOR--5%-060362"))
    )
    (comp (ref "R80")
      (value "62")
      (footprint "eagle-import:0603_1608METRIC")
      (description "RES 62 OHM 1/10W 5% 0603 SMD")
      (fields
        (field (name "DISTRIBUTORPARTNO") "311-62GRCT-ND ")
        (field (name "MANPARTNO") "RC0603JR-0762RL ")
        (field (name "MANUFACTURER") "Yaego")
        (field (name "DISTRIBUTOR") "Digikey")
        (field (name "DISTRIBUTORPARTNO_1") "311-62GRCT-ND ")
        (field (name "MANPARTNO_1") "RC0603JR-0762RL ")
        (field (name "MANUFACTURER_1") "Yaego")
        (field (name "MNT-TYPE") "SM")
        (field (name "NO-PINS") "2")
        (field (name "PACKAGE") "0603 (16080 Metric)")
        (field (name "TOLERANCE") "5%")
      )
      (libsource (lib "eagle-import") (part "RESISTOR--5%-060362"))
    )
    (comp (ref "R81")
      (value "2k")
      (footprint "eagle-import:0603_1608METRIC")
      (fields
        (field (name "DISTRIBUTORPARTNO") "311-2.0KGRCT-ND")
        (field (name "MANPARTNO") "RC0603JR-072KL")
        (field (name "MANUFACTURER") "Yaego")
      )
      (libsource (lib "eagle-import") (part "RESISTOR--5%-06032K"))
    )
    (comp (ref "R82")
      (value "2k")
      (footprint "eagle-import:0603_1608METRIC")
      (fields
        (field (name "DISTRIBUTORPARTNO") "311-2.0KGRCT-ND")
        (field (name "MANPARTNO") "RC0603JR-072KL")
        (field (name "MANUFACTURER") "Yaego")
      )
      (libsource (lib "eagle-import") (part "RESISTOR--5%-06032K"))
    )
    (comp (ref "R83")
      (value "2k")
      (footprint "eagle-import:0603_1608METRIC")
      (fields
        (field (name "DISTRIBUTORPARTNO") "311-2.0KGRCT-ND")
        (field (name "MANPARTNO") "RC0603JR-072KL")
        (field (name "MANUFACTURER") "Yaego")
      )
      (libsource (lib "eagle-import") (part "RESISTOR--5%-06032K"))
    )
    (comp (ref "RX")
      (value "HEADERPIN")
      (footprint "eagle-import:HEADERPIN")
      (libsource (lib "eagle-import") (part "HEADERPIN"))
    )
    (comp (ref "SW1")
      (value "4mm")
      (footprint "eagle-import:PTS645SM43SMTRLFS")
      (fields
        (field (name "DISTRIBUTORPARTNO") "CKN9112CT-ND")
        (field (name "MANPARTNO") "PTS645SM43SMTR LFS")
        (field (name "MANUFACTURER") "C&K Components")
        (field (name "DISTRIBUTORPARTNO_1") "CKN9112CT-ND")
        (field (name "MANPARTNO_1") "PTS645SM43SMTR LFS")
        (field (name "MANUFACTURER_1") "C&K Components")
        (field (name "MNT-TYPE") "SM")
      )
      (libsource (lib "eagle-import") (part "SWITCH-TACT-SM"))
    )
    (comp (ref "SW2")
      (value "4mm")
      (footprint "eagle-import:PTS645SM43SMTRLFS")
      (fields
        (field (name "DISTRIBUTORPARTNO") "CKN9112CT-ND")
        (field (name "MANPARTNO") "PTS645SM43SMTR LFS")
        (field (name "MANUFACTURER") "C&K Components")
        (field (name "DISTRIBUTORPARTNO_1") "CKN9112CT-ND")
        (field (name "MANPARTNO_1") "PTS645SM43SMTR LFS")
        (field (name "MANUFACTURER_1") "C&K Components")
        (field (name "MNT-TYPE") "SM")
      )
      (libsource (lib "eagle-import") (part "SWITCH-TACT-SM"))
    )
    (comp (ref "TX")
      (value "HEADERPIN")
      (footprint "eagle-import:HEADERPIN")
      (libsource (lib "eagle-import") (part "HEADERPIN"))
    )
    (comp (ref "U1")
      (value "74HC595")
      (footprint "eagle-import:SO16")
      (fields
        (field (name "DISTRIBUTORPARTNO") "296-14857-1-ND")
        (field (name "MANPARTNO") "SN74HC595DR")
        (field (name "MANUFACTURER") "Texas Instruments")
      )
      (libsource (lib "eagle-import") (part "74595-SOICHC"))
    )
    (comp (ref "U2")
      (value "74HC595")
      (footprint "eagle-import:SO16")
      (fields
        (field (name "DISTRIBUTORPARTNO") "296-14857-1-ND")
        (field (name "MANPARTNO") "SN74HC595DR")
        (field (name "MANUFACTURER") "Texas Instruments")
      )
      (libsource (lib "eagle-import") (part "74595-SOICHC"))
    )
    (comp (ref "U3")
      (value "74HC595")
      (footprint "eagle-import:SO16")
      (fields
        (field (name "DISTRIBUTORPARTNO") "296-14857-1-ND")
        (field (name "MANPARTNO") "SN74HC595DR")
        (field (name "MANUFACTURER") "Texas Instruments")
      )
      (libsource (lib "eagle-import") (part "74595-SOICHC"))
    )
    (comp (ref "U4")
      (value "74HC595")
      (footprint "eagle-import:SO16")
      (fields
        (field (name "DISTRIBUTORPARTNO") "296-14857-1-ND")
        (field (name "MANPARTNO") "SN74HC595DR")
        (field (name "MANUFACTURER") "Texas Instruments")
      )
      (libsource (lib "eagle-import") (part "74595-SOICHC"))
    )
    (comp (ref "U5")
      (value "74HC595")
      (footprint "eagle-import:SO16")
      (fields
        (field (name "DISTRIBUTORPARTNO") "296-14857-1-ND")
        (field (name "MANPARTNO") "SN74HC595DR")
        (field (name "MANUFACTURER") "Texas Instruments")
      )
      (libsource (lib "eagle-import") (part "74595-SOICHC"))
    )
    (comp (ref "U6")
      (value "74HC595")
      (footprint "eagle-import:SO16")
      (fields
        (field (name "DISTRIBUTORPARTNO") "296-14857-1-ND")
        (field (name "MANPARTNO") "SN74HC595DR")
        (field (name "MANUFACTURER") "Texas Instruments")
      )
      (libsource (lib "eagle-import") (part "74595-SOICHC"))
    )
    (comp (ref "U7")
      (value "ATMega328A")
      (footprint "eagle-import:TQFP-32")
      (fields
        (field (name "DISTRIBUTORPARTNO") "ATMEGA328-AU-ND")
        (field (name "MANPARTNO") "ATMEGA328-AU")
        (field (name "MANUFACTURER") "Atmel")
      )
      (libsource (lib "eagle-import") (part "ATMEGAA328"))
    )
    (comp (ref "U8")
      (value "74HC138")
      (footprint "eagle-import:SO16")
      (fields
        (field (name "DISTRIBUTORPARTNO") "MC74HC138ADGOS-ND")
        (field (name "MANPARTNO") "MC74HC138ADG")
        (field (name "MANUFACTURER") "ON Semiconductor")
      )
      (libsource (lib "eagle-import") (part "74138-SOICHC"))
    )
    (comp (ref "U9")
      (value "74HC14")
      (footprint "eagle-import:SO14")
      (fields
        (field (name "DISTRIBUTORPARTNO") "296-9179-1-ND")
        (field (name "MANPARTNO") "CD74HC14M96")
        (field (name "MANUFACTURER") "Texas Instruments")
      )
      (libsource (lib "eagle-import") (part "7414-SOICHC"))
    )
    (comp (ref "U10")
      (value "74HC595")
      (footprint "eagle-import:SO16")
      (fields
        (field (name "DISTRIBUTORPARTNO") "296-14857-1-ND")
        (field (name "MANPARTNO") "SN74HC595DR")
        (field (name "MANUFACTURER") "Texas Instruments")
      )
      (libsource (lib "eagle-import") (part "74595-SOICHC"))
    )
    (comp (ref "U11")
      (value "74HC595")
      (footprint "eagle-import:SO16")
      (fields
        (field (name "DISTRIBUTORPARTNO") "296-14857-1-ND")
        (field (name "MANPARTNO") "SN74HC595DR")
        (field (name "MANUFACTURER") "Texas Instruments")
      )
      (libsource (lib "eagle-import") (part "74595-SOICHC"))
    )
    (comp (ref "U12")
      (value "74HC595")
      (footprint "eagle-import:SO16")
      (fields
        (field (name "DISTRIBUTORPARTNO") "296-14857-1-ND")
        (field (name "MANPARTNO") "SN74HC595DR")
        (field (name "MANUFACTURER") "Texas Instruments")
      )
      (libsource (lib "eagle-import") (part "74595-SOICHC"))
    )
    (comp (ref "U13")
      (value "74HC14")
      (footprint "eagle-import:SO14")
      (fields
        (field (name "DISTRIBUTORPARTNO") "296-9179-1-ND")
        (field (name "MANPARTNO") "CD74HC14M96")
        (field (name "MANUFACTURER") "Texas Instruments")
      )
      (libsource (lib "eagle-import") (part "7414-SOICHC"))
    )
    (comp (ref "X1")
      (value "11.0592MHz")
      (footprint "eagle-import:HC49UP")
      (description "CRYSTAL 11.0592 MHZ 18PF SMD")
      (fields
        (field (name "DISTRIBUTORPARTNO") "887-1266-1-ND")
        (field (name "MANPARTNO") "9C-11.0592MEEJ-T")
        (field (name "MANUFACTURER") "TXC CORPORATION")
        (field (name "DISTRIBUTOR") "Digikey")
        (field (name "DISTRIBUTORPARTNO_1") "887-1266-1-ND")
        (field (name "MANPARTNO_1") "9C-11.0592MEEJ-T")
        (field (name "MANUFACTURER_1") "TXC CORPORATION")
        (field (name "MNT-TYPE") "SM")
        (field (name "NO-PINS") "2")
        (field (name "PACKAGE") "HC49/US")
      )
      (libsource (lib "eagle-import") (part "XTAL9C-T"))
    )
  )
  (nets
    (net (code "1") (name "+5V") (class "Default")
      (node (ref "C1") (pin "P1") (pinfunction "1_P1") (pintype "passive"))
      (node (ref "C10") (pin "P1") (pinfunction "1_P1") (pintype "passive"))
      (node (ref "C11") (pin "P1") (pinfunction "1_P1") (pintype "passive"))
      (node (ref "C12") (pin "+") (pinfunction "1_+") (pintype "passive"))
      (node (ref "C13") (pin "+") (pinfunction "1_+") (pintype "passive"))
      (node (ref "C14") (pin "+") (pinfunction "1_+") (pintype "passive"))
      (node (ref "C15") (pin "+") (pinfunction "1_+") (pintype "passive"))
      (node (ref "C18") (pin "P1") (pinfunction "1_P1") (pintype "passive"))
      (node (ref "C19") (pin "P1") (pinfunction "1_P1") (pintype "passive"))
      (node (ref "C2") (pin "P1") (pinfunction "1_P1") (pintype "passive"))
      (node (ref "C20") (pin "P1") (pinfunction "1_P1") (pintype "passive"))
      (node (ref "C21") (pin "P1") (pinfunction "1_P1") (pintype "passive"))
      (node (ref "C22") (pin "P1") (pinfunction "1_P1") (pintype "passive"))
      (node (ref "C23") (pin "P1") (pinfunction "1_P1") (pintype "passive"))
      (node (ref "C3") (pin "P1") (pinfunction "1_P1") (pintype "passive"))
      (node (ref "C4") (pin "P1") (pinfunction "1_P1") (pintype "passive"))
      (node (ref "C5") (pin "P1") (pinfunction "1_P1") (pintype "passive"))
      (node (ref "C6") (pin "P1") (pinfunction "1_P1") (pintype "passive"))
      (node (ref "C7") (pin "P1") (pinfunction "1_P1") (pintype "passive"))
      (node (ref "C8") (pin "P1") (pinfunction "1_P1") (pintype "passive"))
      (node (ref "J1") (pin "1") (pinfunction "PIN_1") (pintype "bidirectional"))
      (node (ref "J2") (pin "P2") (pinfunction "VCC_P2") (pintype "bidirectional"))
      (node (ref "R51") (pin "P2") (pinfunction "2_P2") (pintype "passive"))
      (node (ref "R54") (pin "P2") (pinfunction "2_P2") (pintype "passive"))
      (node (ref "R55") (pin "P2") (pinfunction "2_P2") (pintype "passive"))
      (node (ref "U1") (pin "10") (pinfunction "SCL_10") (pintype "input"))
      (node (ref "U1") (pin "16") (pinfunction "VCC_16") (pintype "bidirectional"))
      (node (ref "U10") (pin "10") (pinfunction "SCL_10") (pintype "input"))
      (node (ref "U10") (pin "16") (pinfunction "VCC_16") (pintype "bidirectional"))
      (node (ref "U11") (pin "10") (pinfunction "SCL_10") (pintype "input"))
      (node (ref "U11") (pin "16") (pinfunction "VCC_16") (pintype "bidirectional"))
      (node (ref "U12") (pin "10") (pinfunction "SCL_10") (pintype "input"))
      (node (ref "U12") (pin "16") (pinfunction "VCC_16") (pintype "bidirectional"))
      (node (ref "U13") (pin "14") (pinfunction "VCC_14") (pintype "bidirectional"))
      (node (ref "U2") (pin "10") (pinfunction "SCL_10") (pintype "input"))
      (node (ref "U2") (pin "16") (pinfunction "VCC_16") (pintype "bidirectional"))
      (node (ref "U3") (pin "10") (pinfunction "SCL_10") (pintype "input"))
      (node (ref "U3") (pin "16") (pinfunction "VCC_16") (pintype "bidirectional"))
      (node (ref "U4") (pin "10") (pinfunction "SCL_10") (pintype "input"))
      (node (ref "U4") (pin "16") (pinfunction "VCC_16") (pintype "bidirectional"))
      (node (ref "U5") (pin "10") (pinfunction "SCL_10") (pintype "input"))
      (node (ref "U5") (pin "16") (pinfunction "VCC_16") (pintype "bidirectional"))
      (node (ref "U6") (pin "10") (pinfunction "SCL_10") (pintype "input"))
      (node (ref "U6") (pin "16") (pinfunction "VCC_16") (pintype "bidirectional"))
      (node (ref "U7") (pin "P18") (pinfunction "AVCC_P18") (pintype "bidirectional"))
      (node (ref "U7") (pin "P4") (pinfunction "VCC_P4") (pintype "bidirectional"))
      (node (ref "U7") (pin "P6") (pinfunction "VCC2_P6") (pintype "bidirectional"))
      (node (ref "U8") (pin "16") (pinfunction "VCC_16") (pintype "bidirectional"))
      (node (ref "U8") (pin "6") (pinfunction "G1_6") (pintype "input"))
      (node (ref "U9") (pin "14") (pinfunction "VCC_14") (pintype "bidirectional"))
    )
    (net (code "2") (name "/MISO") (class "Default")
      (node (ref "J2") (pin "P1") (pinfunction "MISO_P1") (pintype "bidirectional"))
      (node (ref "U7") (pin "P16") (pinfunction "(PCINT4/MISO)PB4_P16") (pintype "bidirectional"))
    )
    (net (code "3") (name "/MOSI") (class "Default")
      (node (ref "J2") (pin "P4") (pinfunction "MOSI_P4") (pintype "bidirectional"))
      (node (ref "U7") (pin "P15") (pinfunction "(PCINT3/OC2A/MOSI)PB3_P15") (pintype "bidirectional"))
    )
    (net (code "4") (name "/PSCK") (class "Default")
      (node (ref "J2") (pin "P3") (pinfunction "SCK_P3") (pintype "bidirectional"))
      (node (ref "U7") (pin "P17") (pinfunction "(SCK/PCINT5)PB5_P17") (pintype "bidirectional"))
    )
    (net (code "5") (name "/RCK") (class "Default")
      (node (ref "U1") (pin "12") (pinfunction "RCK_12") (pintype "input"))
      (node (ref "U10") (pin "12") (pinfunction "RCK_12") (pintype "input"))
      (node (ref "U11") (pin "12") (pinfunction "RCK_12") (pintype "input"))
      (node (ref "U12") (pin "12") (pinfunction "RCK_12") (pintype "input"))
      (node (ref "U2") (pin "12") (pinfunction "RCK_12") (pintype "input"))
      (node (ref "U3") (pin "12") (pinfunction "RCK_12") (pintype "input"))
      (node (ref "U4") (pin "12") (pinfunction "RCK_12") (pintype "input"))
      (node (ref "U5") (pin "12") (pinfunction "RCK_12") (pintype "input"))
      (node (ref "U6") (pin "12") (pinfunction "RCK_12") (pintype "input"))
      (node (ref "U7") (pin "P25") (pinfunction "PC2(ADC2/PCINT10)_P25") (pintype "bidirectional"))
    )
    (net (code "6") (name "/ROW0") (class "Default")
      (node (ref "D1") (pin "P9") (pinfunction "R1_P9") (pintype "bidirectional"))
      (node (ref "D10") (pin "P9") (pinfunction "R1_P9") (pintype "bidirectional"))
      (node (ref "D2") (pin "P9") (pinfunction "R1_P9") (pintype "bidirectional"))
      (node (ref "D3") (pin "P9") (pinfunction "R1_P9") (pintype "bidirectional"))
      (node (ref "D4") (pin "P9") (pinfunction "R1_P9") (pintype "bidirectional"))
      (node (ref "D5") (pin "P9") (pinfunction "R1_P9") (pintype "bidirectional"))
      (node (ref "D6") (pin "P9") (pinfunction "R1_P9") (pintype "bidirectional"))
      (node (ref "D8") (pin "P9") (pinfunction "R1_P9") (pintype "bidirectional"))
      (node (ref "D9") (pin "P9") (pinfunction "R1_P9") (pintype "bidirectional"))
      (node (ref "Q1") (pin "3") (pinfunction "D_3") (pintype "bidirectional"))
    )
    (net (code "7") (name "/ROW1") (class "Default")
      (node (ref "D1") (pin "P14") (pinfunction "R2_P14") (pintype "bidirectional"))
      (node (ref "D10") (pin "P14") (pinfunction "R2_P14") (pintype "bidirectional"))
      (node (ref "D2") (pin "P14") (pinfunction "R2_P14") (pintype "bidirectional"))
      (node (ref "D3") (pin "P14") (pinfunction "R2_P14") (pintype "bidirectional"))
      (node (ref "D4") (pin "P14") (pinfunction "R2_P14") (pintype "bidirectional"))
      (node (ref "D5") (pin "P14") (pinfunction "R2_P14") (pintype "bidirectional"))
      (node (ref "D6") (pin "P14") (pinfunction "R2_P14") (pintype "bidirectional"))
      (node (ref "D8") (pin "P14") (pinfunction "R2_P14") (pintype "bidirectional"))
      (node (ref "D9") (pin "P14") (pinfunction "R2_P14") (pintype "bidirectional"))
      (node (ref "Q2") (pin "3") (pinfunction "D_3") (pintype "bidirectional"))
    )
    (net (code "8") (name "/ROW2") (class "Default")
      (node (ref "D1") (pin "P8") (pinfunction "R3_P8") (pintype "bidirectional"))
      (node (ref "D10") (pin "P8") (pinfunction "R3_P8") (pintype "bidirectional"))
      (node (ref "D2") (pin "P8") (pinfunction "R3_P8") (pintype "bidirectional"))
      (node (ref "D3") (pin "P8") (pinfunction "R3_P8") (pintype "bidirectional"))
      (node (ref "D4") (pin "P8") (pinfunction "R3_P8") (pintype "bidirectional"))
      (node (ref "D5") (pin "P8") (pinfunction "R3_P8") (pintype "bidirectional"))
      (node (ref "D6") (pin "P8") (pinfunction "R3_P8") (pintype "bidirectional"))
      (node (ref "D8") (pin "P8") (pinfunction "R3_P8") (pintype "bidirectional"))
      (node (ref "D9") (pin "P8") (pinfunction "R3_P8") (pintype "bidirectional"))
      (node (ref "Q3") (pin "3") (pinfunction "D_3") (pintype "bidirectional"))
    )
    (net (code "9") (name "/ROW3") (class "Default")
      (node (ref "D1") (pin "P12") (pinfunction "R4_P12") (pintype "bidirectional"))
      (node (ref "D10") (pin "P12") (pinfunction "R4_P12") (pintype "bidirectional"))
      (node (ref "D2") (pin "P12") (pinfunction "R4_P12") (pintype "bidirectional"))
      (node (ref "D3") (pin "P12") (pinfunction "R4_P12") (pintype "bidirectional"))
      (node (ref "D4") (pin "P12") (pinfunction "R4_P12") (pintype "bidirectional"))
      (node (ref "D5") (pin "P12") (pinfunction "R4_P12") (pintype "bidirectional"))
      (node (ref "D6") (pin "P12") (pinfunction "R4_P12") (pintype "bidirectional"))
      (node (ref "D8") (pin "P12") (pinfunction "R4_P12") (pintype "bidirectional"))
      (node (ref "D9") (pin "P12") (pinfunction "R4_P12") (pintype "bidirectional"))
      (node (ref "Q4") (pin "3") (pinfunction "D_3") (pintype "bidirectional"))
    )
    (net (code "10") (name "/ROW4") (class "Default")
      (node (ref "D1") (pin "P1") (pinfunction "R5_P1") (pintype "bidirectional"))
      (node (ref "D10") (pin "P1") (pinfunction "R5_P1") (pintype "bidirectional"))
      (node (ref "D2") (pin "P1") (pinfunction "R5_P1") (pintype "bidirectional"))
      (node (ref "D3") (pin "P1") (pinfunction "R5_P1") (pintype "bidirectional"))
      (node (ref "D4") (pin "P1") (pinfunction "R5_P1") (pintype "bidirectional"))
      (node (ref "D5") (pin "P1") (pinfunction "R5_P1") (pintype "bidirectional"))
      (node (ref "D6") (pin "P1") (pinfunction "R5_P1") (pintype "bidirectional"))
      (node (ref "D8") (pin "P1") (pinfunction "R5_P1") (pintype "bidirectional"))
      (node (ref "D9") (pin "P1") (pinfunction "R5_P1") (pintype "bidirectional"))
      (node (ref "Q5") (pin "3") (pinfunction "D_3") (pintype "bidirectional"))
    )
    (net (code "11") (name "/ROW5") (class "Default")
      (node (ref "D1") (pin "P7") (pinfunction "R6_P7") (pintype "bidirectional"))
      (node (ref "D10") (pin "P7") (pinfunction "R6_P7") (pintype "bidirectional"))
      (node (ref "D2") (pin "P7") (pinfunction "R6_P7") (pintype "bidirectional"))
      (node (ref "D3") (pin "P7") (pinfunction "R6_P7") (pintype "bidirectional"))
      (node (ref "D4") (pin "P7") (pinfunction "R6_P7") (pintype "bidirectional"))
      (node (ref "D5") (pin "P7") (pinfunction "R6_P7") (pintype "bidirectional"))
      (node (ref "D6") (pin "P7") (pinfunction "R6_P7") (pintype "bidirectional"))
      (node (ref "D8") (pin "P7") (pinfunction "R6_P7") (pintype "bidirectional"))
      (node (ref "D9") (pin "P7") (pinfunction "R6_P7") (pintype "bidirectional"))
      (node (ref "Q6") (pin "3") (pinfunction "D_3") (pintype "bidirectional"))
    )
    (net (code "12") (name "/ROW6") (class "Default")
      (node (ref "D1") (pin "P2") (pinfunction "R7_P2") (pintype "bidirectional"))
      (node (ref "D10") (pin "P2") (pinfunction "R7_P2") (pintype "bidirectional"))
      (node (ref "D2") (pin "P2") (pinfunction "R7_P2") (pintype "bidirectional"))
      (node (ref "D3") (pin "P2") (pinfunction "R7_P2") (pintype "bidirectional"))
      (node (ref "D4") (pin "P2") (pinfunction "R7_P2") (pintype "bidirectional"))
      (node (ref "D5") (pin "P2") (pinfunction "R7_P2") (pintype "bidirectional"))
      (node (ref "D6") (pin "P2") (pinfunction "R7_P2") (pintype "bidirectional"))
      (node (ref "D8") (pin "P2") (pinfunction "R7_P2") (pintype "bidirectional"))
      (node (ref "D9") (pin "P2") (pinfunction "R7_P2") (pintype "bidirectional"))
      (node (ref "Q7") (pin "3") (pinfunction "D_3") (pintype "bidirectional"))
    )
    (net (code "13") (name "/ROW7") (class "Default")
      (node (ref "D1") (pin "P5") (pinfunction "R8_P5") (pintype "bidirectional"))
      (node (ref "D10") (pin "P5") (pinfunction "R8_P5") (pintype "bidirectional"))
      (node (ref "D2") (pin "P5") (pinfunction "R8_P5") (pintype "bidirectional"))
      (node (ref "D3") (pin "P5") (pinfunction "R8_P5") (pintype "bidirectional"))
      (node (ref "D4") (pin "P5") (pinfunction "R8_P5") (pintype "bidirectional"))
      (node (ref "D5") (pin "P5") (pinfunction "R8_P5") (pintype "bidirectional"))
      (node (ref "D6") (pin "P5") (pinfunction "R8_P5") (pintype "bidirectional"))
      (node (ref "D8") (pin "P5") (pinfunction "R8_P5") (pintype "bidirectional"))
      (node (ref "D9") (pin "P5") (pinfunction "R8_P5") (pintype "bidirectional"))
      (node (ref "Q8") (pin "3") (pinfunction "D_3") (pintype "bidirectional"))
    )
    (net (code "14") (name "/SCK") (class "Default")
      (node (ref "U1") (pin "11") (pinfunction "SCK_11") (pintype "input"))
      (node (ref "U10") (pin "11") (pinfunction "SCK_11") (pintype "input"))
      (node (ref "U11") (pin "11") (pinfunction "SCK_11") (pintype "input"))
      (node (ref "U12") (pin "11") (pinfunction "SCK_11") (pintype "input"))
      (node (ref "U2") (pin "11") (pinfunction "SCK_11") (pintype "input"))
      (node (ref "U3") (pin "11") (pinfunction "SCK_11") (pintype "input"))
      (node (ref "U4") (pin "11") (pinfunction "SCK_11") (pintype "input"))
      (node (ref "U5") (pin "11") (pinfunction "SCK_11") (pintype "input"))
      (node (ref "U6") (pin "11") (pinfunction "SCK_11") (pintype "input"))
      (node (ref "U7") (pin "P32") (pinfunction "PD2(INT0/PCINT18)_P32") (pintype "bidirectional"))
    )
    (net (code "15") (name "/SDATA1") (class "Default")
      (node (ref "U1") (pin "14") (pinfunction "SER_14") (pintype "input"))
      (node (ref "U7") (pin "P27") (pinfunction "PC4(ADC4/SDA/PCINT12)_P27") (pintype "bidirectional"))
    )
    (net (code "16") (name "/SDATA2") (class "Default")
      (node (ref "U4") (pin "14") (pinfunction "SER_14") (pintype "input"))
      (node (ref "U7") (pin "P26") (pinfunction "PC3(ADC3/PCINT11)_P26") (pintype "bidirectional"))
    )
    (net (code "17") (name "/SDATA3") (class "Default")
      (node (ref "U10") (pin "14") (pinfunction "SER_14") (pintype "input"))
      (node (ref "U7") (pin "P28") (pinfunction "PC5(ADC5/SCL/PCINT13)_P28") (pintype "bidirectional"))
    )
    (net (code "18") (name "/~{OE}") (class "Default")
      (node (ref "R54") (pin "P1") (pinfunction "1_P1") (pintype "passive"))
      (node (ref "U1") (pin "13") (pinfunction "G_13") (pintype "input"))
      (node (ref "U10") (pin "13") (pinfunction "G_13") (pintype "input"))
      (node (ref "U11") (pin "13") (pinfunction "G_13") (pintype "input"))
      (node (ref "U12") (pin "13") (pinfunction "G_13") (pintype "input"))
      (node (ref "U2") (pin "13") (pinfunction "G_13") (pintype "input"))
      (node (ref "U3") (pin "13") (pinfunction "G_13") (pintype "input"))
      (node (ref "U4") (pin "13") (pinfunction "G_13") (pintype "input"))
      (node (ref "U5") (pin "13") (pinfunction "G_13") (pintype "input"))
      (node (ref "U6") (pin "13") (pinfunction "G_13") (pintype "input"))
      (node (ref "U7") (pin "P10") (pinfunction "PD6(PCINT22/OC0A/AIN0)_P10") (pintype "bidirectional"))
    )
    (net (code "19") (name "/~{RESET}") (class "Default")
      (node (ref "J2") (pin "P5") (pinfunction "~{RESET}_P5") (pintype "bidirectional"))
      (node (ref "R55") (pin "P1") (pinfunction "1_P1") (pintype "passive"))
      (node (ref "U7") (pin "P29") (pinfunction "PC6(RESET/PCINT14)_P29") (pintype "bidirectional"))
    )
    (net (code "20") (name "GND") (class "Default")
      (node (ref "C1") (pin "P2") (pinfunction "2_P2") (pintype "passive"))
      (node (ref "C10") (pin "P2") (pinfunction "2_P2") (pintype "passive"))
      (node (ref "C11") (pin "P2") (pinfunction "2_P2") (pintype "passive"))
      (node (ref "C12") (pin "-") (pinfunction "2_-") (pintype "passive"))
      (node (ref "C13") (pin "-") (pinfunction "2_-") (pintype "passive"))
      (node (ref "C14") (pin "-") (pinfunction "2_-") (pintype "passive"))
      (node (ref "C15") (pin "-") (pinfunction "2_-") (pintype "passive"))
      (node (ref "C16") (pin "P2") (pinfunction "2_P2") (pintype "passive"))
      (node (ref "C17") (pin "P2") (pinfunction "2_P2") (pintype "passive"))
      (node (ref "C18") (pin "P2") (pinfunction "2_P2") (pintype "passive"))
      (node (ref "C19") (pin "P2") (pinfunction "2_P2") (pintype "passive"))
      (node (ref "C2") (pin "P2") (pinfunction "2_P2") (pintype "passive"))
      (node (ref "C20") (pin "P2") (pinfunction "2_P2") (pintype "passive"))
      (node (ref "C21") (pin "P2") (pinfunction "2_P2") (pintype "passive"))
      (node (ref "C22") (pin "P2") (pinfunction "2_P2") (pintype "passive"))
      (node (ref "C23") (pin "P2") (pinfunction "2_P2") (pintype "passive"))
      (node (ref "C3") (pin "P2") (pinfunction "2_P2") (pintype "passive"))
      (node (ref "C4") (pin "P2") (pinfunction "2_P2") (pintype "passive"))
      (node (ref "C5") (pin "P2") (pinfunction "2_P2") (pintype "passive"))
      (node (ref "C6") (pin "P2") (pinfunction "2_P2") (pintype "passive"))
      (node (ref "C7") (pin "P2") (pinfunction "2_P2") (pintype "passive"))
      (node (ref "C8") (pin "P2") (pinfunction "2_P2") (pintype "passive"))
      (node (ref "C9") (pin "P2") (pinfunction "2_P2") (pintype "passive"))
      (node (ref "D7") (pin "K") (pinfunction "C_K") (pintype "passive"))
      (node (ref "GND") (pin "P$1") (pinfunction "P$1_P$1") (pintype "bidirectional"))
      (node (ref "J1") (pin "2") (pinfunction "BARREL_2") (pintype "bidirectional"))
      (node (ref "J2") (pin "P6") (pinfunction "GND_P6") (pintype "bidirectional"))
      (node (ref "Q1") (pin "2") (pinfunction "S_2") (pintype "bidirectional"))
      (node (ref "Q2") (pin "2") (pinfunction "S_2") (pintype "bidirectional"))
      (node (ref "Q3") (pin "2") (pinfunction "S_2") (pintype "bidirectional"))
      (node (ref "Q4") (pin "2") (pinfunction "S_2") (pintype "bidirectional"))
      (node (ref "Q5") (pin "2") (pinfunction "S_2") (pintype "bidirectional"))
      (node (ref "Q6") (pin "2") (pinfunction "S_2") (pintype "bidirectional"))
      (node (ref "Q7") (pin "2") (pinfunction "S_2") (pintype "bidirectional"))
      (node (ref "Q8") (pin "2") (pinfunction "S_2") (pintype "bidirectional"))
      (node (ref "SW1") (pin "P3") (pinfunction "P3_P3") (pintype "bidirectional"))
      (node (ref "SW1") (pin "P4") (pinfunction "P4_P4") (pintype "bidirectional"))
      (node (ref "SW2") (pin "P3") (pinfunction "P3_P3") (pintype "bidirectional"))
      (node (ref "SW2") (pin "P4") (pinfunction "P4_P4") (pintype "bidirectional"))
      (node (ref "U1") (pin "8") (pinfunction "GND_8") (pintype "bidirectional"))
      (node (ref "U10") (pin "8") (pinfunction "GND_8") (pintype "bidirectional"))
      (node (ref "U11") (pin "8") (pinfunction "GND_8") (pintype "bidirectional"))
      (node (ref "U12") (pin "8") (pinfunction "GND_8") (pintype "bidirectional"))
      (node (ref "U13") (pin "11") (pinfunction "I_11") (pintype "input"))
      (node (ref "U13") (pin "13") (pinfunction "I_13") (pintype "input"))
      (node (ref "U13") (pin "7") (pinfunction "GND_7") (pintype "bidirectional"))
      (node (ref "U2") (pin "8") (pinfunction "GND_8") (pintype "bidirectional"))
      (node (ref "U3") (pin "8") (pinfunction "GND_8") (pintype "bidirectional"))
      (node (ref "U4") (pin "8") (pinfunction "GND_8") (pintype "bidirectional"))
      (node (ref "U5") (pin "8") (pinfunction "GND_8") (pintype "bidirectional"))
      (node (ref "U6") (pin "8") (pinfunction "GND_8") (pintype "bidirectional"))
      (node (ref "U7") (pin "P21") (pinfunction "GND3_P21") (pintype "bidirectional"))
      (node (ref "U7") (pin "P3") (pinfunction "GND_P3") (pintype "bidirectional"))
      (node (ref "U7") (pin "P5") (pinfunction "GND2_P5") (pintype "bidirectional"))
      (node (ref "U8") (pin "4") (pinfunction "G2A_4") (pintype "input"))
      (node (ref "U8") (pin "5") (pinfunction "G2B_5") (pintype "input"))
      (node (ref "U8") (pin "8") (pinfunction "GND_8") (pintype "bidirectional"))
      (node (ref "U9") (pin "11") (pinfunction "I_11") (pintype "input"))
      (node (ref "U9") (pin "13") (pinfunction "I_13") (pintype "input"))
      (node (ref "U9") (pin "7") (pinfunction "GND_7") (pintype "bidirectional"))
    )
    (net (code "21") (name "Net-(C9-1)") (class "Default")
      (node (ref "C9") (pin "P1") (pinfunction "1_P1") (pintype "passive"))
      (node (ref "U7") (pin "P20") (pinfunction "AREF_P20") (pintype "bidirectional"))
    )
    (net (code "22") (name "Net-(C16-1)") (class "Default")
      (node (ref "C16") (pin "P1") (pinfunction "1_P1") (pintype "passive"))
      (node (ref "U7") (pin "P8") (pinfunction "(PCINT7/XTAL2/TOSC2)PB7_P8") (pintype "bidirectional"))
      (node (ref "X1") (pin "2") (pinfunction "2_2") (pintype "passive"))
    )
    (net (code "23") (name "Net-(C17-1)") (class "Default")
      (node (ref "C17") (pin "P1") (pinfunction "1_P1") (pintype "passive"))
      (node (ref "U7") (pin "P7") (pinfunction "(PCINT6/XTAL1/TOSC1)PB6_P7") (pintype "bidirectional"))
      (node (ref "X1") (pin "1") (pinfunction "1_1") (pintype "passive"))
    )
    (net (code "24") (name "Net-(D1-C1)") (class "Default")
      (node (ref "D1") (pin "P13") (pinfunction "C1_P13") (pintype "bidirectional"))
      (node (ref "R1") (pin "P1") (pinfunction "1_P1") (pintype "passive"))
    )
    (net (code "25") (name "Net-(D1-C2)") (class "Default")
      (node (ref "D1") (pin "P3") (pinfunction "C2_P3") (pintype "bidirectional"))
      (node (ref "R2") (pin "P1") (pinfunction "1_P1") (pintype "passive"))
    )
    (net (code "26") (name "Net-(D1-C3)") (class "Default")
      (node (ref "D1") (pin "P4") (pinfunction "C3_P4") (pintype "bidirectional"))
      (node (ref "R3") (pin "P1") (pinfunction "1_P1") (pintype "passive"))
    )
    (net (code "27") (name "Net-(D1-C4)") (class "Default")
      (node (ref "D1") (pin "P10") (pinfunction "C4_P10") (pintype "bidirectional"))
      (node (ref "R4") (pin "P1") (pinfunction "1_P1") (pintype "passive"))
    )
    (net (code "28") (name "Net-(D1-C5)") (class "Default")
      (node (ref "D1") (pin "P6") (pinfunction "C5_P6") (pintype "bidirectional"))
      (node (ref "R5") (pin "P1") (pinfunction "1_P1") (pintype "passive"))
    )
    (net (code "29") (name "Net-(D1-C6)") (class "Default")
      (node (ref "D1") (pin "P11") (pinfunction "C6_P11") (pintype "bidirectional"))
      (node (ref "R6") (pin "P1") (pinfunction "1_P1") (pintype "passive"))
    )
    (net (code "30") (name "Net-(D1-C7)") (class "Default")
      (node (ref "D1") (pin "P15") (pinfunction "C7_P15") (pintype "bidirectional"))
      (node (ref "R7") (pin "P1") (pinfunction "1_P1") (pintype "passive"))
    )
    (net (code "31") (name "Net-(D1-C8)") (class "Default")
      (node (ref "D1") (pin "P16") (pinfunction "C8_P16") (pintype "bidirectional"))
      (node (ref "R8") (pin "P1") (pinfunction "1_P1") (pintype "passive"))
    )
    (net (code "32") (name "Net-(D2-C1)") (class "Default")
      (node (ref "D2") (pin "P13") (pinfunction "C1_P13") (pintype "bidirectional"))
      (node (ref "R9") (pin "P1") (pinfunction "1_P1") (pintype "passive"))
    )
    (net (code "33") (name "Net-(D2-C2)") (class "Default")
      (node (ref "D2") (pin "P3") (pinfunction "C2_P3") (pintype "bidirectional"))
      (node (ref "R10") (pin "P1") (pinfunction "1_P1") (pintype "passive"))
    )
    (net (code "34") (name "Net-(D2-C3)") (class "Default")
      (node (ref "D2") (pin "P4") (pinfunction "C3_P4") (pintype "bidirectional"))
      (node (ref "R11") (pin "P1") (pinfunction "1_P1") (pintype "passive"))
    )
    (net (code "35") (name "Net-(D2-C4)") (class "Default")
      (node (ref "D2") (pin "P10") (pinfunction "C4_P10") (pintype "bidirectional"))
      (node (ref "R12") (pin "P1") (pinfunction "1_P1") (pintype "passive"))
    )
    (net (code "36") (name "Net-(D2-C5)") (class "Default")
      (node (ref "D2") (pin "P6") (pinfunction "C5_P6") (pintype "bidirectional"))
      (node (ref "R13") (pin "P1") (pinfunction "1_P1") (pintype "passive"))
    )
    (net (code "37") (name "Net-(D2-C6)") (class "Default")
      (node (ref "D2") (pin "P11") (pinfunction "C6_P11") (pintype "bidirectional"))
      (node (ref "R14") (pin "P1") (pinfunction "1_P1") (pintype "passive"))
    )
    (net (code "38") (name "Net-(D2-C7)") (class "Default")
      (node (ref "D2") (pin "P15") (pinfunction "C7_P15") (pintype "bidirectional"))
      (node (ref "R15") (pin "P1") (pinfunction "1_P1") (pintype "passive"))
    )
    (net (code "39") (name "Net-(D2-C8)") (class "Default")
      (node (ref "D2") (pin "P16") (pinfunction "C8_P16") (pintype "bidirectional"))
      (node (ref "R16") (pin "P1") (pinfunction "1_P1") (pintype "passive"))
    )
    (net (code "40") (name "Net-(D3-C1)") (class "Default")
      (node (ref "D3") (pin "P13") (pinfunction "C1_P13") (pintype "bidirectional"))
      (node (ref "R17") (pin "P1") (pinfunction "1_P1") (pintype "passive"))
    )
    (net (code "41") (name "Net-(D3-C2)") (class "Default")
      (node (ref "D3") (pin "P3") (pinfunction "C2_P3") (pintype "bidirectional"))
      (node (ref "R18") (pin "P1") (pinfunction "1_P1") (pintype "passive"))
    )
    (net (code "42") (name "Net-(D3-C3)") (class "Default")
      (node (ref "D3") (pin "P4") (pinfunction "C3_P4") (pintype "bidirectional"))
      (node (ref "R19") (pin "P1") (pinfunction "1_P1") (pintype "passive"))
    )
    (net (code "43") (name "Net-(D3-C4)") (class "Default")
      (node (ref "D3") (pin "P10") (pinfunction "C4_P10") (pintype "bidirectional"))
      (node (ref "R20") (pin "P1") (pinfunction "1_P1") (pintype "passive"))
    )
    (net (code "44") (name "Net-(D3-C5)") (class "Default")
      (node (ref "D3") (pin "P6") (pinfunction "C5_P6") (pintype "bidirectional"))
      (node (ref "R21") (pin "P1") (pinfunction "1_P1") (pintype "passive"))
    )
    (net (code "45") (name "Net-(D3-C6)") (class "Default")
      (node (ref "D3") (pin "P11") (pinfunction "C6_P11") (pintype "bidirectional"))
      (node (ref "R22") (pin "P1") (pinfunction "1_P1") (pintype "passive"))
    )
    (net (code "46") (name "Net-(D3-C7)") (class "Default")
      (node (ref "D3") (pin "P15") (pinfunction "C7_P15") (pintype "bidirectional"))
      (node (ref "R23") (pin "P1") (pinfunction "1_P1") (pintype "passive"))
    )
    (net (code "47") (name "Net-(D3-C8)") (class "Default")
      (node (ref "D3") (pin "P16") (pinfunction "C8_P16") (pintype "bidirectional"))
      (node (ref "R24") (pin "P1") (pinfunction "1_P1") (pintype "passive"))
    )
    (net (code "48") (name "Net-(D4-C1)") (class "Default")
      (node (ref "D4") (pin "P13") (pinfunction "C1_P13") (pintype "bidirectional"))
      (node (ref "R25") (pin "P2") (pinfunction "2_P2") (pintype "passive"))
    )
    (net (code "49") (name "Net-(D4-C2)") (class "Default")
      (node (ref "D4") (pin "P3") (pinfunction "C2_P3") (pintype "bidirectional"))
      (node (ref "R26") (pin "P2") (pinfunction "2_P2") (pintype "passive"))
    )
    (net (code "50") (name "Net-(D4-C3)") (class "Default")
      (node (ref "D4") (pin "P4") (pinfunction "C3_P4") (pintype "bidirectional"))
      (node (ref "R27") (pin "P2") (pinfunction "2_P2") (pintype "passive"))
    )
    (net (code "51") (name "Net-(D4-C4)") (class "Default")
      (node (ref "D4") (pin "P10") (pinfunction "C4_P10") (pintype "bidirectional"))
      (node (ref "R28") (pin "P2") (pinfunction "2_P2") (pintype "passive"))
    )
    (net (code "52") (name "Net-(D4-C5)") (class "Default")
      (node (ref "D4") (pin "P6") (pinfunction "C5_P6") (pintype "bidirectional"))
      (node (ref "R29") (pin "P2") (pinfunction "2_P2") (pintype "passive"))
    )
    (net (code "53") (name "Net-(D4-C6)") (class "Default")
      (node (ref "D4") (pin "P11") (pinfunction "C6_P11") (pintype "bidirectional"))
      (node (ref "R30") (pin "P2") (pinfunction "2_P2") (pintype "passive"))
    )
    (net (code "54") (name "Net-(D4-C7)") (class "Default")
      (node (ref "D4") (pin "P15") (pinfunction "C7_P15") (pintype "bidirectional"))
      (node (ref "R31") (pin "P2") (pinfunction "2_P2") (pintype "passive"))
    )
    (net (code "55") (name "Net-(D4-C8)") (class "Default")
      (node (ref "D4") (pin "P16") (pinfunction "C8_P16") (pintype "bidirectional"))
      (node (ref "R32") (pin "P2") (pinfunction "2_P2") (pintype "passive"))
    )
    (net (code "56") (name "Net-(D5-C1)") (class "Default")
      (node (ref "D5") (pin "P13") (pinfunction "C1_P13") (pintype "bidirectional"))
      (node (ref "R33") (pin "P2") (pinfunction "2_P2") (pintype "passive"))
    )
    (net (code "57") (name "Net-(D5-C2)") (class "Default")
      (node (ref "D5") (pin "P3") (pinfunction "C2_P3") (pintype "bidirectional"))
      (node (ref "R34") (pin "P2") (pinfunction "2_P2") (pintype "passive"))
    )
    (net (code "58") (name "Net-(D5-C3)") (class "Default")
      (node (ref "D5") (pin "P4") (pinfunction "C3_P4") (pintype "bidirectional"))
      (node (ref "R35") (pin "P2") (pinfunction "2_P2") (pintype "passive"))
    )
    (net (code "59") (name "Net-(D5-C4)") (class "Default")
      (node (ref "D5") (pin "P10") (pinfunction "C4_P10") (pintype "bidirectional"))
      (node (ref "R36") (pin "P2") (pinfunction "2_P2") (pintype "passive"))
    )
    (net (code "60") (name "Net-(D5-C5)") (class "Default")
      (node (ref "D5") (pin "P6") (pinfunction "C5_P6") (pintype "bidirectional"))
      (node (ref "R37") (pin "P2") (pinfunction "2_P2") (pintype "passive"))
    )
    (net (code "61") (name "Net-(D5-C6)") (class "Default")
      (node (ref "D5") (pin "P11") (pinfunction "C6_P11") (pintype "bidirectional"))
      (node (ref "R38") (pin "P2") (pinfunction "2_P2") (pintype "passive"))
    )
    (net (code "62") (name "Net-(D5-C7)") (class "Default")
      (node (ref "D5") (pin "P15") (pinfunction "C7_P15") (pintype "bidirectional"))
      (node (ref "R39") (pin "P2") (pinfunction "2_P2") (pintype "passive"))
    )
    (net (code "63") (name "Net-(D5-C8)") (class "Default")
      (node (ref "D5") (pin "P16") (pinfunction "C8_P16") (pintype "bidirectional"))
      (node (ref "R40") (pin "P2") (pinfunction "2_P2") (pintype "passive"))
    )
    (net (code "64") (name "Net-(D6-C1)") (class "Default")
      (node (ref "D6") (pin "P13") (pinfunction "C1_P13") (pintype "bidirectional"))
      (node (ref "R41") (pin "P2") (pinfunction "2_P2") (pintype "passive"))
    )
    (net (code "65") (name "Net-(D6-C2)") (class "Default")
      (node (ref "D6") (pin "P3") (pinfunction "C2_P3") (pintype "bidirectional"))
      (node (ref "R42") (pin "P2") (pinfunction "2_P2") (pintype "passive"))
    )
    (net (code "66") (name "Net-(D6-C3)") (class "Default")
      (node (ref "D6") (pin "P4") (pinfunction "C3_P4") (pintype "bidirectional"))
      (node (ref "R43") (pin "P2") (pinfunction "2_P2") (pintype "passive"))
    )
    (net (code "67") (name "Net-(D6-C4)") (class "Default")
      (node (ref "D6") (pin "P10") (pinfunction "C4_P10") (pintype "bidirectional"))
      (node (ref "R44") (pin "P2") (pinfunction "2_P2") (pintype "passive"))
    )
    (net (code "68") (name "Net-(D6-C5)") (class "Default")
      (node (ref "D6") (pin "P6") (pinfunction "C5_P6") (pintype "bidirectional"))
      (node (ref "R45") (pin "P2") (pinfunction "2_P2") (pintype "passive"))
    )
    (net (code "69") (name "Net-(D6-C6)") (class "Default")
      (node (ref "D6") (pin "P11") (pinfunction "C6_P11") (pintype "bidirectional"))
      (node (ref "R46") (pin "P2") (pinfunction "2_P2") (pintype "passive"))
    )
    (net (code "70") (name "Net-(D6-C7)") (class "Default")
      (node (ref "D6") (pin "P15") (pinfunction "C7_P15") (pintype "bidirectional"))
      (node (ref "R47") (pin "P2") (pinfunction "2_P2") (pintype "passive"))
    )
    (net (code "71") (name "Net-(D6-C8)") (class "Default")
      (node (ref "D6") (pin "P16") (pinfunction "C8_P16") (pintype "bidirectional"))
      (node (ref "R48") (pin "P2") (pinfunction "2_P2") (pintype "passive"))
    )
    (net (code "72") (name "Net-(D8-C1)") (class "Default")
      (node (ref "D8") (pin "P13") (pinfunction "C1_P13") (pintype "bidirectional"))
      (node (ref "R57") (pin "P2") (pinfunction "2_P2") (pintype "passive"))
    )
    (net (code "73") (name "Net-(D8-C2)") (class "Default")
      (node (ref "D8") (pin "P3") (pinfunction "C2_P3") (pintype "bidirectional"))
      (node (ref "R58") (pin "P2") (pinfunction "2_P2") (pintype "passive"))
    )
    (net (code "74") (name "Net-(D8-C3)") (class "Default")
      (node (ref "D8") (pin "P4") (pinfunction "C3_P4") (pintype "bidirectional"))
      (node (ref "R59") (pin "P2") (pinfunction "2_P2") (pintype "passive"))
    )
    (net (code "75") (name "Net-(D8-C4)") (class "Default")
      (node (ref "D8") (pin "P10") (pinfunction "C4_P10") (pintype "bidirectional"))
      (node (ref "R60") (pin "P2") (pinfunction "2_P2") (pintype "passive"))
    )
    (net (code "76") (name "Net-(D8-C5)") (class "Default")
      (node (ref "D8") (pin "P6") (pinfunction "C5_P6") (pintype "bidirectional"))
      (node (ref "R61") (pin "P2") (pinfunction "2_P2") (pintype "passive"))
    )
    (net (code "77") (name "Net-(D8-C6)") (class "Default")
      (node (ref "D8") (pin "P11") (pinfunction "C6_P11") (pintype "bidirectional"))
      (node (ref "R62") (pin "P2") (pinfunction "2_P2") (pintype "passive"))
    )
    (net (code "78") (name "Net-(D8-C7)") (class "Default")
      (node (ref "D8") (pin "P15") (pinfunction "C7_P15") (pintype "bidirectional"))
      (node (ref "R63") (pin "P2") (pinfunction "2_P2") (pintype "passive"))
    )
    (net (code "79") (name "Net-(D8-C8)") (class "Default")
      (node (ref "D8") (pin "P16") (pinfunction "C8_P16") (pintype "bidirectional"))
      (node (ref "R64") (pin "P2") (pinfunction "2_P2") (pintype "passive"))
    )
    (net (code "80") (name "Net-(D9-C1)") (class "Default")
      (node (ref "D9") (pin "P13") (pinfunction "C1_P13") (pintype "bidirectional"))
      (node (ref "R65") (pin "P2") (pinfunction "2_P2") (pintype "passive"))
    )
    (net (code "81") (name "Net-(D9-C2)") (class "Default")
      (node (ref "D9") (pin "P3") (pinfunction "C2_P3") (pintype "bidirectional"))
      (node (ref "R66") (pin "P2") (pinfunction "2_P2") (pintype "passive"))
    )
    (net (code "82") (name "Net-(D9-C3)") (class "Default")
      (node (ref "D9") (pin "P4") (pinfunction "C3_P4") (pintype "bidirectional"))
      (node (ref "R67") (pin "P2") (pinfunction "2_P2") (pintype "passive"))
    )
    (net (code "83") (name "Net-(D9-C4)") (class "Default")
      (node (ref "D9") (pin "P10") (pinfunction "C4_P10") (pintype "bidirectional"))
      (node (ref "R68") (pin "P2") (pinfunction "2_P2") (pintype "passive"))
    )
    (net (code "84") (name "Net-(D9-C5)") (class "Default")
      (node (ref "D9") (pin "P6") (pinfunction "C5_P6") (pintype "bidirectional"))
      (node (ref "R69") (pin "P2") (pinfunction "2_P2") (pintype "passive"))
    )
    (net (code "85") (name "Net-(D9-C6)") (class "Default")
      (node (ref "D9") (pin "P11") (pinfunction "C6_P11") (pintype "bidirectional"))
      (node (ref "R70") (pin "P2") (pinfunction "2_P2") (pintype "passive"))
    )
    (net (code "86") (name "Net-(D9-C7)") (class "Default")
      (node (ref "D9") (pin "P15") (pinfunction "C7_P15") (pintype "bidirectional"))
      (node (ref "R71") (pin "P2") (pinfunction "2_P2") (pintype "passive"))
    )
    (net (code "87") (name "Net-(D9-C8)") (class "Default")
      (node (ref "D9") (pin "P16") (pinfunction "C8_P16") (pintype "bidirectional"))
      (node (ref "R72") (pin "P2") (pinfunction "2_P2") (pintype "passive"))
    )
    (net (code "88") (name "Net-(D10-C1)") (class "Default")
      (node (ref "D10") (pin "P13") (pinfunction "C1_P13") (pintype "bidirectional"))
      (node (ref "R73") (pin "P2") (pinfunction "2_P2") (pintype "passive"))
    )
    (net (code "89") (name "Net-(D10-C2)") (class "Default")
      (node (ref "D10") (pin "P3") (pinfunction "C2_P3") (pintype "bidirectional"))
      (node (ref "R74") (pin "P2") (pinfunction "2_P2") (pintype "passive"))
    )
    (net (code "90") (name "Net-(D10-C3)") (class "Default")
      (node (ref "D10") (pin "P4") (pinfunction "C3_P4") (pintype "bidirectional"))
      (node (ref "R75") (pin "P2") (pinfunction "2_P2") (pintype "passive"))
    )
    (net (code "91") (name "Net-(D10-C4)") (class "Default")
      (node (ref "D10") (pin "P10") (pinfunction "C4_P10") (pintype "bidirectional"))
      (node (ref "R76") (pin "P2") (pinfunction "2_P2") (pintype "passive"))
    )
    (net (code "92") (name "Net-(D10-C5)") (class "Default")
      (node (ref "D10") (pin "P6") (pinfunction "C5_P6") (pintype "bidirectional"))
      (node (ref "R77") (pin "P2") (pinfunction "2_P2") (pintype "passive"))
    )
    (net (code "93") (name "Net-(D10-C6)") (class "Default")
      (node (ref "D10") (pin "P11") (pinfunction "C6_P11") (pintype "bidirectional"))
      (node (ref "R78") (pin "P2") (pinfunction "2_P2") (pintype "passive"))
    )
    (net (code "94") (name "Net-(D10-C7)") (class "Default")
      (node (ref "D10") (pin "P15") (pinfunction "C7_P15") (pintype "bidirectional"))
      (node (ref "R79") (pin "P2") (pinfunction "2_P2") (pintype "passive"))
    )
    (net (code "95") (name "Net-(D10-C8)") (class "Default")
      (node (ref "D10") (pin "P16") (pinfunction "C8_P16") (pintype "bidirectional"))
      (node (ref "R80") (pin "P2") (pinfunction "2_P2") (pintype "passive"))
    )
    (net (code "96") (name "Net-(Q1-G)") (class "Default")
      (node (ref "Q1") (pin "1") (pinfunction "G_1") (pintype "bidirectional"))
      (node (ref "R49") (pin "P2") (pinfunction "2_P2") (pintype "passive"))
    )
    (net (code "97") (name "Net-(Q2-G)") (class "Default")
      (node (ref "Q2") (pin "1") (pinfunction "G_1") (pintype "bidirectional"))
      (node (ref "R50") (pin "P2") (pinfunction "2_P2") (pintype "passive"))
    )
    (net (code "98") (name "Net-(Q3-G)") (class "Default")
      (node (ref "Q3") (pin "1") (pinfunction "G_1") (pintype "bidirectional"))
      (node (ref "R52") (pin "P2") (pinfunction "2_P2") (pintype "passive"))
    )
    (net (code "99") (name "Net-(Q4-G)") (class "Default")
      (node (ref "Q4") (pin "1") (pinfunction "G_1") (pintype "bidirectional"))
      (node (ref "R53") (pin "P2") (pinfunction "2_P2") (pintype "passive"))
    )
    (net (code "100") (name "Net-(Q5-G)") (class "Default")
      (node (ref "Q5") (pin "1") (pinfunction "G_1") (pintype "bidirectional"))
      (node (ref "R56") (pin "P2") (pinfunction "2_P2") (pintype "passive"))
    )
    (net (code "101") (name "Net-(Q6-G)") (class "Default")
      (node (ref "Q6") (pin "1") (pinfunction "G_1") (pintype "bidirectional"))
      (node (ref "R81") (pin "P2") (pinfunction "2_P2") (pintype "passive"))
    )
    (net (code "102") (name "Net-(Q7-G)") (class "Default")
      (node (ref "Q7") (pin "1") (pinfunction "G_1") (pintype "bidirectional"))
      (node (ref "R82") (pin "P2") (pinfunction "2_P2") (pintype "passive"))
    )
    (net (code "103") (name "Net-(Q8-G)") (class "Default")
      (node (ref "Q8") (pin "1") (pinfunction "G_1") (pintype "bidirectional"))
      (node (ref "R83") (pin "P2") (pinfunction "2_P2") (pintype "passive"))
    )
    (net (code "104") (name "Net-(R1-2)") (class "Default")
      (node (ref "R1") (pin "P2") (pinfunction "2_P2") (pintype "passive"))
      (node (ref "U1") (pin "7") (pinfunction "QH_7") (pintype "tri_state"))
    )
    (net (code "105") (name "Net-(R2-2)") (class "Default")
      (node (ref "R2") (pin "P2") (pinfunction "2_P2") (pintype "passive"))
      (node (ref "U1") (pin "4") (pinfunction "QE_4") (pintype "tri_state"))
    )
    (net (code "106") (name "Net-(R3-2)") (class "Default")
      (node (ref "R3") (pin "P2") (pinfunction "2_P2") (pintype "passive"))
      (node (ref "U1") (pin "3") (pinfunction "QD_3") (pintype "tri_state"))
    )
    (net (code "107") (name "Net-(R4-2)") (class "Default")
      (node (ref "R4") (pin "P2") (pinfunction "2_P2") (pintype "passive"))
      (node (ref "U1") (pin "1") (pinfunction "QB_1") (pintype "tri_state"))
    )
    (net (code "108") (name "Net-(R5-2)") (class "Default")
      (node (ref "R5") (pin "P2") (pinfunction "2_P2") (pintype "passive"))
      (node (ref "U1") (pin "2") (pinfunction "QC_2") (pintype "tri_state"))
    )
    (net (code "109") (name "Net-(R6-2)") (class "Default")
      (node (ref "R6") (pin "P2") (pinfunction "2_P2") (pintype "passive"))
      (node (ref "U1") (pin "15") (pinfunction "QA_15") (pintype "tri_state"))
    )
    (net (code "110") (name "Net-(R7-2)") (class "Default")
      (node (ref "R7") (pin "P2") (pinfunction "2_P2") (pintype "passive"))
      (node (ref "U1") (pin "6") (pinfunction "QG_6") (pintype "tri_state"))
    )
    (net (code "111") (name "Net-(R8-2)") (class "Default")
      (node (ref "R8") (pin "P2") (pinfunction "2_P2") (pintype "passive"))
      (node (ref "U1") (pin "5") (pinfunction "QF_5") (pintype "tri_state"))
    )
    (net (code "112") (name "Net-(R9-2)") (class "Default")
      (node (ref "R9") (pin "P2") (pinfunction "2_P2") (pintype "passive"))
      (node (ref "U2") (pin "7") (pinfunction "QH_7") (pintype "tri_state"))
    )
    (net (code "113") (name "Net-(R10-2)") (class "Default")
      (node (ref "R10") (pin "P2") (pinfunction "2_P2") (pintype "passive"))
      (node (ref "U2") (pin "4") (pinfunction "QE_4") (pintype "tri_state"))
    )
    (net (code "114") (name "Net-(R11-2)") (class "Default")
      (node (ref "R11") (pin "P2") (pinfunction "2_P2") (pintype "passive"))
      (node (ref "U2") (pin "3") (pinfunction "QD_3") (pintype "tri_state"))
    )
    (net (code "115") (name "Net-(R12-2)") (class "Default")
      (node (ref "R12") (pin "P2") (pinfunction "2_P2") (pintype "passive"))
      (node (ref "U2") (pin "1") (pinfunction "QB_1") (pintype "tri_state"))
    )
    (net (code "116") (name "Net-(R13-2)") (class "Default")
      (node (ref "R13") (pin "P2") (pinfunction "2_P2") (pintype "passive"))
      (node (ref "U2") (pin "2") (pinfunction "QC_2") (pintype "tri_state"))
    )
    (net (code "117") (name "Net-(R14-2)") (class "Default")
      (node (ref "R14") (pin "P2") (pinfunction "2_P2") (pintype "passive"))
      (node (ref "U2") (pin "15") (pinfunction "QA_15") (pintype "tri_state"))
    )
    (net (code "118") (name "Net-(R15-2)") (class "Default")
      (node (ref "R15") (pin "P2") (pinfunction "2_P2") (pintype "passive"))
      (node (ref "U2") (pin "6") (pinfunction "QG_6") (pintype "tri_state"))
    )
    (net (code "119") (name "Net-(R16-2)") (class "Default")
      (node (ref "R16") (pin "P2") (pinfunction "2_P2") (pintype "passive"))
      (node (ref "U2") (pin "5") (pinfunction "QF_5") (pintype "tri_state"))
    )
    (net (code "120") (name "Net-(R17-2)") (class "Default")
      (node (ref "R17") (pin "P2") (pinfunction "2_P2") (pintype "passive"))
      (node (ref "U3") (pin "7") (pinfunction "QH_7") (pintype "tri_state"))
    )
    (net (code "121") (name "Net-(R18-2)") (class "Default")
      (node (ref "R18") (pin "P2") (pinfunction "2_P2") (pintype "passive"))
      (node (ref "U3") (pin "4") (pinfunction "QE_4") (pintype "tri_state"))
    )
    (net (code "122") (name "Net-(R19-2)") (class "Default")
      (node (ref "R19") (pin "P2") (pinfunction "2_P2") (pintype "passive"))
      (node (ref "U3") (pin "3") (pinfunction "QD_3") (pintype "tri_state"))
    )
    (net (code "123") (name "Net-(R20-2)") (class "Default")
      (node (ref "R20") (pin "P2") (pinfunction "2_P2") (pintype "passive"))
      (node (ref "U3") (pin "1") (pinfunction "QB_1") (pintype "tri_state"))
    )
    (net (code "124") (name "Net-(R21-2)") (class "Default")
      (node (ref "R21") (pin "P2") (pinfunction "2_P2") (pintype "passive"))
      (node (ref "U3") (pin "2") (pinfunction "QC_2") (pintype "tri_state"))
    )
    (net (code "125") (name "Net-(R22-2)") (class "Default")
      (node (ref "R22") (pin "P2") (pinfunction "2_P2") (pintype "passive"))
      (node (ref "U3") (pin "15") (pinfunction "QA_15") (pintype "tri_state"))
    )
    (net (code "126") (name "Net-(R23-2)") (class "Default")
      (node (ref "R23") (pin "P2") (pinfunction "2_P2") (pintype "passive"))
      (node (ref "U3") (pin "6") (pinfunction "QG_6") (pintype "tri_state"))
    )
    (net (code "127") (name "Net-(R24-2)") (class "Default")
      (node (ref "R24") (pin "P2") (pinfunction "2_P2") (pintype "passive"))
      (node (ref "U3") (pin "5") (pinfunction "QF_5") (pintype "tri_state"))
    )
    (net (code "128") (name "Net-(R25-1)") (class "Default")
      (node (ref "R25") (pin "P1") (pinfunction "1_P1") (pintype "passive"))
      (node (ref "U4") (pin "7") (pinfunction "QH_7") (pintype "tri_state"))
    )
    (net (code "129") (name "Net-(R26-1)") (class "Default")
      (node (ref "R26") (pin "P1") (pinfunction "1_P1") (pintype "passive"))
      (node (ref "U4") (pin "4") (pinfunction "QE_4") (pintype "tri_state"))
    )
    (net (code "130") (name "Net-(R27-1)") (class "Default")
      (node (ref "R27") (pin "P1") (pinfunction "1_P1") (pintype "passive"))
      (node (ref "U4") (pin "3") (pinfunction "QD_3") (pintype "tri_state"))
    )
    (net (code "131") (name "Net-(R28-1)") (class "Default")
      (node (ref "R28") (pin "P1") (pinfunction "1_P1") (pintype "passive"))
      (node (ref "U4") (pin "1") (pinfunction "QB_1") (pintype "tri_state"))
    )
    (net (code "132") (name "Net-(R29-1)") (class "Default")
      (node (ref "R29") (pin "P1") (pinfunction "1_P1") (pintype "passive"))
      (node (ref "U4") (pin "2") (pinfunction "QC_2") (pintype "tri_state"))
    )
    (net (code "133") (name "Net-(R30-1)") (class "Default")
      (node (ref "R30") (pin "P1") (pinfunction "1_P1") (pintype "passive"))
      (node (ref "U4") (pin "15") (pinfunction "QA_15") (pintype "tri_state"))
    )
    (net (code "134") (name "Net-(R31-1)") (class "Default")
      (node (ref "R31") (pin "P1") (pinfunction "1_P1") (pintype "passive"))
      (node (ref "U4") (pin "6") (pinfunction "QG_6") (pintype "tri_state"))
    )
    (net (code "135") (name "Net-(R32-1)") (class "Default")
      (node (ref "R32") (pin "P1") (pinfunction "1_P1") (pintype "passive"))
      (node (ref "U4") (pin "5") (pinfunction "QF_5") (pintype "tri_state"))
    )
    (net (code "136") (name "Net-(R33-1)") (class "Default")
      (node (ref "R33") (pin "P1") (pinfunction "1_P1") (pintype "passive"))
      (node (ref "U5") (pin "7") (pinfunction "QH_7") (pintype "tri_state"))
    )
    (net (code "137") (name "Net-(R34-1)") (class "Default")
      (node (ref "R34") (pin "P1") (pinfunction "1_P1") (pintype "passive"))
      (node (ref "U5") (pin "4") (pinfunction "QE_4") (pintype "tri_state"))
    )
    (net (code "138") (name "Net-(R35-1)") (class "Default")
      (node (ref "R35") (pin "P1") (pinfunction "1_P1") (pintype "passive"))
      (node (ref "U5") (pin "3") (pinfunction "QD_3") (pintype "tri_state"))
    )
    (net (code "139") (name "Net-(R36-1)") (class "Default")
      (node (ref "R36") (pin "P1") (pinfunction "1_P1") (pintype "passive"))
      (node (ref "U5") (pin "1") (pinfunction "QB_1") (pintype "tri_state"))
    )
    (net (code "140") (name "Net-(R37-1)") (class "Default")
      (node (ref "R37") (pin "P1") (pinfunction "1_P1") (pintype "passive"))
      (node (ref "U5") (pin "2") (pinfunction "QC_2") (pintype "tri_state"))
    )
    (net (code "141") (name "Net-(R38-1)") (class "Default")
      (node (ref "R38") (pin "P1") (pinfunction "1_P1") (pintype "passive"))
      (node (ref "U5") (pin "15") (pinfunction "QA_15") (pintype "tri_state"))
    )
    (net (code "142") (name "Net-(R39-1)") (class "Default")
      (node (ref "R39") (pin "P1") (pinfunction "1_P1") (pintype "passive"))
      (node (ref "U5") (pin "6") (pinfunction "QG_6") (pintype "tri_state"))
    )
    (net (code "143") (name "Net-(R40-1)") (class "Default")
      (node (ref "R40") (pin "P1") (pinfunction "1_P1") (pintype "passive"))
      (node (ref "U5") (pin "5") (pinfunction "QF_5") (pintype "tri_state"))
    )
    (net (code "144") (name "Net-(R41-1)") (class "Default")
      (node (ref "R41") (pin "P1") (pinfunction "1_P1") (pintype "passive"))
      (node (ref "U6") (pin "7") (pinfunction "QH_7") (pintype "tri_state"))
    )
    (net (code "145") (name "Net-(R42-1)") (class "Default")
      (node (ref "R42") (pin "P1") (pinfunction "1_P1") (pintype "passive"))
      (node (ref "U6") (pin "4") (pinfunction "QE_4") (pintype "tri_state"))
    )
    (net (code "146") (name "Net-(R43-1)") (class "Default")
      (node (ref "R43") (pin "P1") (pinfunction "1_P1") (pintype "passive"))
      (node (ref "U6") (pin "3") (pinfunction "QD_3") (pintype "tri_state"))
    )
    (net (code "147") (name "Net-(R44-1)") (class "Default")
      (node (ref "R44") (pin "P1") (pinfunction "1_P1") (pintype "passive"))
      (node (ref "U6") (pin "1") (pinfunction "QB_1") (pintype "tri_state"))
    )
    (net (code "148") (name "Net-(R45-1)") (class "Default")
      (node (ref "R45") (pin "P1") (pinfunction "1_P1") (pintype "passive"))
      (node (ref "U6") (pin "2") (pinfunction "QC_2") (pintype "tri_state"))
    )
    (net (code "149") (name "Net-(R46-1)") (class "Default")
      (node (ref "R46") (pin "P1") (pinfunction "1_P1") (pintype "passive"))
      (node (ref "U6") (pin "15") (pinfunction "QA_15") (pintype "tri_state"))
    )
    (net (code "150") (name "Net-(R47-1)") (class "Default")
      (node (ref "R47") (pin "P1") (pinfunction "1_P1") (pintype "passive"))
      (node (ref "U6") (pin "6") (pinfunction "QG_6") (pintype "tri_state"))
    )
    (net (code "151") (name "Net-(R48-1)") (class "Default")
      (node (ref "R48") (pin "P1") (pinfunction "1_P1") (pintype "passive"))
      (node (ref "U6") (pin "5") (pinfunction "QF_5") (pintype "tri_state"))
    )
    (net (code "152") (name "Net-(R49-1)") (class "Default")
      (node (ref "R49") (pin "P1") (pinfunction "1_P1") (pintype "passive"))
      (node (ref "U9") (pin "8") (pinfunction "O_8") (pintype "output"))
    )
    (net (code "153") (name "Net-(R50-1)") (class "Default")
      (node (ref "R50") (pin "P1") (pinfunction "1_P1") (pintype "passive"))
      (node (ref "U9") (pin "6") (pinfunction "O_6") (pintype "output"))
    )
    (net (code "154") (name "Net-(R51-1)") (class "Default")
      (node (ref "D7") (pin "A") (pinfunction "A_A") (pintype "passive"))
      (node (ref "R51") (pin "P1") (pinfunction "1_P1") (pintype "passive"))
      (node (ref "U7") (pin "P22") (pinfunction "ADC7_P22") (pintype "bidirectional"))
    )
    (net (code "155") (name "Net-(R52-1)") (class "Default")
      (node (ref "R52") (pin "P1") (pinfunction "1_P1") (pintype "passive"))
      (node (ref "U9") (pin "2") (pinfunction "O_2") (pintype "output"))
    )
    (net (code "156") (name "Net-(R53-1)") (class "Default")
      (node (ref "R53") (pin "P1") (pinfunction "1_P1") (pintype "passive"))
      (node (ref "U9") (pin "4") (pinfunction "O_4") (pintype "output"))
    )
    (net (code "157") (name "Net-(R56-1)") (class "Default")
      (node (ref "R56") (pin "P1") (pinfunction "1_P1") (pintype "passive"))
      (node (ref "U13") (pin "6") (pinfunction "O_6") (pintype "output"))
    )
    (net (code "158") (name "Net-(R57-1)") (class "Default")
      (node (ref "R57") (pin "P1") (pinfunction "1_P1") (pintype "passive"))
      (node (ref "U10") (pin "7") (pinfunction "QH_7") (pintype "tri_state"))
    )
    (net (code "159") (name "Net-(R58-1)") (class "Default")
      (node (ref "R58") (pin "P1") (pinfunction "1_P1") (pintype "passive"))
      (node (ref "U10") (pin "4") (pinfunction "QE_4") (pintype "tri_state"))
    )
    (net (code "160") (name "Net-(R59-1)") (class "Default")
      (node (ref "R59") (pin "P1") (pinfunction "1_P1") (pintype "passive"))
      (node (ref "U10") (pin "3") (pinfunction "QD_3") (pintype "tri_state"))
    )
    (net (code "161") (name "Net-(R60-1)") (class "Default")
      (node (ref "R60") (pin "P1") (pinfunction "1_P1") (pintype "passive"))
      (node (ref "U10") (pin "1") (pinfunction "QB_1") (pintype "tri_state"))
    )
    (net (code "162") (name "Net-(R61-1)") (class "Default")
      (node (ref "R61") (pin "P1") (pinfunction "1_P1") (pintype "passive"))
      (node (ref "U10") (pin "2") (pinfunction "QC_2") (pintype "tri_state"))
    )
    (net (code "163") (name "Net-(R62-1)") (class "Default")
      (node (ref "R62") (pin "P1") (pinfunction "1_P1") (pintype "passive"))
      (node (ref "U10") (pin "15") (pinfunction "QA_15") (pintype "tri_state"))
    )
    (net (code "164") (name "Net-(R63-1)") (class "Default")
      (node (ref "R63") (pin "P1") (pinfunction "1_P1") (pintype "passive"))
      (node (ref "U10") (pin "6") (pinfunction "QG_6") (pintype "tri_state"))
    )
    (net (code "165") (name "Net-(R64-1)") (class "Default")
      (node (ref "R64") (pin "P1") (pinfunction "1_P1") (pintype "passive"))
      (node (ref "U10") (pin "5") (pinfunction "QF_5") (pintype "tri_state"))
    )
    (net (code "166") (name "Net-(R65-1)") (class "Default")
      (node (ref "R65") (pin "P1") (pinfunction "1_P1") (pintype "passive"))
      (node (ref "U11") (pin "7") (pinfunction "QH_7") (pintype "tri_state"))
    )
    (net (code "167") (name "Net-(R66-1)") (class "Default")
      (node (ref "R66") (pin "P1") (pinfunction "1_P1") (pintype "passive"))
      (node (ref "U11") (pin "4") (pinfunction "QE_4") (pintype "tri_state"))
    )
    (net (code "168") (name "Net-(R67-1)") (class "Default")
      (node (ref "R67") (pin "P1") (pinfunction "1_P1") (pintype "passive"))
      (node (ref "U11") (pin "3") (pinfunction "QD_3") (pintype "tri_state"))
    )
    (net (code "169") (name "Net-(R68-1)") (class "Default")
      (node (ref "R68") (pin "P1") (pinfunction "1_P1") (pintype "passive"))
      (node (ref "U11") (pin "1") (pinfunction "QB_1") (pintype "tri_state"))
    )
    (net (code "170") (name "Net-(R69-1)") (class "Default")
      (node (ref "R69") (pin "P1") (pinfunction "1_P1") (pintype "passive"))
      (node (ref "U11") (pin "2") (pinfunction "QC_2") (pintype "tri_state"))
    )
    (net (code "171") (name "Net-(R70-1)") (class "Default")
      (node (ref "R70") (pin "P1") (pinfunction "1_P1") (pintype "passive"))
      (node (ref "U11") (pin "15") (pinfunction "QA_15") (pintype "tri_state"))
    )
    (net (code "172") (name "Net-(R71-1)") (class "Default")
      (node (ref "R71") (pin "P1") (pinfunction "1_P1") (pintype "passive"))
      (node (ref "U11") (pin "6") (pinfunction "QG_6") (pintype "tri_state"))
    )
    (net (code "173") (name "Net-(R72-1)") (class "Default")
      (node (ref "R72") (pin "P1") (pinfunction "1_P1") (pintype "passive"))
      (node (ref "U11") (pin "5") (pinfunction "QF_5") (pintype "tri_state"))
    )
    (net (code "174") (name "Net-(R73-1)") (class "Default")
      (node (ref "R73") (pin "P1") (pinfunction "1_P1") (pintype "passive"))
      (node (ref "U12") (pin "7") (pinfunction "QH_7") (pintype "tri_state"))
    )
    (net (code "175") (name "Net-(R74-1)") (class "Default")
      (node (ref "R74") (pin "P1") (pinfunction "1_P1") (pintype "passive"))
      (node (ref "U12") (pin "4") (pinfunction "QE_4") (pintype "tri_state"))
    )
    (net (code "176") (name "Net-(R75-1)") (class "Default")
      (node (ref "R75") (pin "P1") (pinfunction "1_P1") (pintype "passive"))
      (node (ref "U12") (pin "3") (pinfunction "QD_3") (pintype "tri_state"))
    )
    (net (code "177") (name "Net-(R76-1)") (class "Default")
      (node (ref "R76") (pin "P1") (pinfunction "1_P1") (pintype "passive"))
      (node (ref "U12") (pin "1") (pinfunction "QB_1") (pintype "tri_state"))
    )
    (net (code "178") (name "Net-(R77-1)") (class "Default")
      (node (ref "R77") (pin "P1") (pinfunction "1_P1") (pintype "passive"))
      (node (ref "U12") (pin "2") (pinfunction "QC_2") (pintype "tri_state"))
    )
    (net (code "179") (name "Net-(R78-1)") (class "Default")
      (node (ref "R78") (pin "P1") (pinfunction "1_P1") (pintype "passive"))
      (node (ref "U12") (pin "15") (pinfunction "QA_15") (pintype "tri_state"))
    )
    (net (code "180") (name "Net-(R79-1)") (class "Default")
      (node (ref "R79") (pin "P1") (pinfunction "1_P1") (pintype "passive"))
      (node (ref "U12") (pin "6") (pinfunction "QG_6") (pintype "tri_state"))
    )
    (net (code "181") (name "Net-(R80-1)") (class "Default")
      (node (ref "R80") (pin "P1") (pinfunction "1_P1") (pintype "passive"))
      (node (ref "U12") (pin "5") (pinfunction "QF_5") (pintype "tri_state"))
    )
    (net (code "182") (name "Net-(R81-1)") (class "Default")
      (node (ref "R81") (pin "P1") (pinfunction "1_P1") (pintype "passive"))
      (node (ref "U13") (pin "8") (pinfunction "O_8") (pintype "output"))
    )
    (net (code "183") (name "Net-(R82-1)") (class "Default")
      (node (ref "R82") (pin "P1") (pinfunction "1_P1") (pintype "passive"))
      (node (ref "U13") (pin "2") (pinfunction "O_2") (pintype "output"))
    )
    (net (code "184") (name "Net-(R83-1)") (class "Default")
      (node (ref "R83") (pin "P1") (pinfunction "1_P1") (pintype "passive"))
      (node (ref "U13") (pin "4") (pinfunction "O_4") (pintype "output"))
    )
    (net (code "185") (name "Net-(U1-QH*)") (class "Default")
      (node (ref "U1") (pin "9") (pinfunction "QH*_9") (pintype "tri_state"))
      (node (ref "U2") (pin "14") (pinfunction "SER_14") (pintype "input"))
    )
    (net (code "186") (name "Net-(U2-QH*)") (class "Default")
      (node (ref "U2") (pin "9") (pinfunction "QH*_9") (pintype "tri_state"))
      (node (ref "U3") (pin "14") (pinfunction "SER_14") (pintype "input"))
    )
    (net (code "187") (name "Net-(U4-QH*)") (class "Default")
      (node (ref "U4") (pin "9") (pinfunction "QH*_9") (pintype "tri_state"))
      (node (ref "U5") (pin "14") (pinfunction "SER_14") (pintype "input"))
    )
    (net (code "188") (name "Net-(U5-QH*)") (class "Default")
      (node (ref "U5") (pin "9") (pinfunction "QH*_9") (pintype "tri_state"))
      (node (ref "U6") (pin "14") (pinfunction "SER_14") (pintype "input"))
    )
    (net (code "189") (name "Net-(U7-(PCINT0{slash}CLKO{slash}ICP1)PB0)") (class "Default")
      (node (ref "U7") (pin "P12") (pinfunction "(PCINT0/CLKO/ICP1)PB0_P12") (pintype "bidirectional"))
      (node (ref "U8") (pin "3") (pinfunction "C_3") (pintype "input"))
    )
    (net (code "190") (name "Net-(U7-(PCINT1{slash}OC1A)PB1)") (class "Default")
      (node (ref "U7") (pin "P13") (pinfunction "(PCINT1/OC1A)PB1_P13") (pintype "bidirectional"))
      (node (ref "U8") (pin "2") (pinfunction "B_2") (pintype "input"))
    )
    (net (code "191") (name "Net-(U7-(PCINT2{slash}SS{slash}OC1B)PB2)") (class "Default")
      (node (ref "U7") (pin "P14") (pinfunction "(PCINT2/SS/OC1B)PB2_P14") (pintype "bidirectional"))
      (node (ref "U8") (pin "1") (pinfunction "A_1") (pintype "input"))
    )
    (net (code "192") (name "Net-(U7-PC0(ADC0{slash}PCINT8))") (class "Default")
      (node (ref "SW1") (pin "P2") (pinfunction "P2_P2") (pintype "bidirectional"))
      (node (ref "U7") (pin "P23") (pinfunction "PC0(ADC0/PCINT8)_P23") (pintype "bidirectional"))
    )
    (net (code "193") (name "Net-(U7-PC1(ADC1{slash}PCINT9))") (class "Default")
      (node (ref "SW2") (pin "P2") (pinfunction "P2_P2") (pintype "bidirectional"))
      (node (ref "U7") (pin "P24") (pinfunction "PC1(ADC1/PCINT9)_P24") (pintype "bidirectional"))
    )
    (net (code "194") (name "Net-(U7-PD0(RXD{slash}PCINT16))") (class "Default")
      (node (ref "RX") (pin "P$1") (pinfunction "P$1_P$1") (pintype "bidirectional"))
      (node (ref "U7") (pin "P30") (pinfunction "PD0(RXD/PCINT16)_P30") (pintype "bidirectional"))
    )
    (net (code "195") (name "Net-(U7-PD1(TXD{slash}PCINT17))") (class "Default")
      (node (ref "TX") (pin "P$1") (pinfunction "P$1_P$1") (pintype "bidirectional"))
      (node (ref "U7") (pin "P31") (pinfunction "PD1(TXD/PCINT17)_P31") (pintype "bidirectional"))
    )
    (net (code "196") (name "Net-(U8-Y0)") (class "Default")
      (node (ref "U8") (pin "15") (pinfunction "Y0_15") (pintype "output"))
      (node (ref "U9") (pin "9") (pinfunction "I_9") (pintype "input"))
    )
    (net (code "197") (name "Net-(U8-Y1)") (class "Default")
      (node (ref "U8") (pin "14") (pinfunction "Y1_14") (pintype "output"))
      (node (ref "U9") (pin "5") (pinfunction "I_5") (pintype "input"))
    )
    (net (code "198") (name "Net-(U8-Y2)") (class "Default")
      (node (ref "U8") (pin "13") (pinfunction "Y2_13") (pintype "output"))
      (node (ref "U9") (pin "1") (pinfunction "I_1") (pintype "input"))
    )
    (net (code "199") (name "Net-(U8-Y3)") (class "Default")
      (node (ref "U8") (pin "12") (pinfunction "Y3_12") (pintype "output"))
      (node (ref "U9") (pin "3") (pinfunction "I_3") (pintype "input"))
    )
    (net (code "200") (name "Net-(U10-QH*)") (class "Default")
      (node (ref "U10") (pin "9") (pinfunction "QH*_9") (pintype "tri_state"))
      (node (ref "U11") (pin "14") (pinfunction "SER_14") (pintype "input"))
    )
    (net (code "201") (name "Net-(U11-QH*)") (class "Default")
      (node (ref "U11") (pin "9") (pinfunction "QH*_9") (pintype "tri_state"))
      (node (ref "U12") (pin "14") (pinfunction "SER_14") (pintype "input"))
    )
    (net (code "202") (name "Net-(U13C-I)") (class "Default")
      (node (ref "U13") (pin "9") (pinfunction "I_9") (pintype "input"))
      (node (ref "U8") (pin "10") (pinfunction "Y5_10") (pintype "output"))
    )
    (net (code "203") (name "Net-(U13D-I)") (class "Default")
      (node (ref "U13") (pin "1") (pinfunction "I_1") (pintype "input"))
      (node (ref "U8") (pin "9") (pinfunction "Y6_9") (pintype "output"))
    )
    (net (code "204") (name "Net-(U13E-I)") (class "Default")
      (node (ref "U13") (pin "3") (pinfunction "I_3") (pintype "input"))
      (node (ref "U8") (pin "7") (pinfunction "Y7_7") (pintype "output"))
    )
    (net (code "205") (name "Net-(U13F-I)") (class "Default")
      (node (ref "U13") (pin "5") (pinfunction "I_5") (pintype "input"))
      (node (ref "U8") (pin "11") (pinfunction "Y4_11") (pintype "output"))
    )
    (net (code "206") (name "unconnected-(J1-SWITCH-Pad3)") (class "Default")
      (node (ref "J1") (pin "3") (pinfunction "SWITCH_3") (pintype "bidirectional"))
    )
    (net (code "207") (name "unconnected-(SW1-PadP1)") (class "Default")
      (node (ref "SW1") (pin "P1") (pinfunction "P1_P1") (pintype "bidirectional"))
    )
    (net (code "208") (name "unconnected-(SW2-PadP1)") (class "Default")
      (node (ref "SW2") (pin "P1") (pinfunction "P1_P1") (pintype "bidirectional"))
    )
    (net (code "209") (name "unconnected-(U3-QH*-Pad9)") (class "Default")
      (node (ref "U3") (pin "9") (pinfunction "QH*_9") (pintype "tri_state"))
    )
    (net (code "210") (name "unconnected-(U6-QH*-Pad9)") (class "Default")
      (node (ref "U6") (pin "9") (pinfunction "QH*_9") (pintype "tri_state"))
    )
    (net (code "211") (name "unconnected-(U7-ADC6-PadP19)") (class "Default")
      (node (ref "U7") (pin "P19") (pinfunction "ADC6_P19") (pintype "bidirectional"))
    )
    (net (code "212") (name "unconnected-(U7-PD3(PCINT19{slash}OC2B{slash}INT1)-PadP1)") (class "Default")
      (node (ref "U7") (pin "P1") (pinfunction "PD3(PCINT19/OC2B/INT1)_P1") (pintype "bidirectional"))
    )
    (net (code "213") (name "unconnected-(U7-PD4(PCINT20{slash}XCK{slash}T0)-PadP2)") (class "Default")
      (node (ref "U7") (pin "P2") (pinfunction "PD4(PCINT20/XCK/T0)_P2") (pintype "bidirectional"))
    )
    (net (code "214") (name "unconnected-(U7-PD5(PCINT21{slash}OC0B{slash}T1)-PadP9)") (class "Default")
      (node (ref "U7") (pin "P9") (pinfunction "PD5(PCINT21/OC0B/T1)_P9") (pintype "bidirectional"))
    )
    (net (code "215") (name "unconnected-(U7-PD7(PCINT23{slash}AIN1)-PadP11)") (class "Default")
      (node (ref "U7") (pin "P11") (pinfunction "PD7(PCINT23/AIN1)_P11") (pintype "bidirectional"))
    )
    (net (code "216") (name "unconnected-(U9A-O-Pad12)") (class "Default")
      (node (ref "U9") (pin "12") (pinfunction "O_12") (pintype "output"))
    )
    (net (code "217") (name "unconnected-(U9B-O-Pad10)") (class "Default")
      (node (ref "U9") (pin "10") (pinfunction "O_10") (pintype "output"))
    )
    (net (code "218") (name "unconnected-(U12-QH*-Pad9)") (class "Default")
      (node (ref "U12") (pin "9") (pinfunction "QH*_9") (pintype "tri_state"))
    )
    (net (code "219") (name "unconnected-(U13A-O-Pad12)") (class "Default")
      (node (ref "U13") (pin "12") (pinfunction "O_12") (pintype "output"))
    )
    (net (code "220") (name "unconnected-(U13B-O-Pad10)") (class "Default")
      (node (ref "U13") (pin "10") (pinfunction "O_10") (pintype "output"))
    )
  )
)
